# CyDAQ_schematic.net
KiCad netlist of a schematic drawn in EAGLE
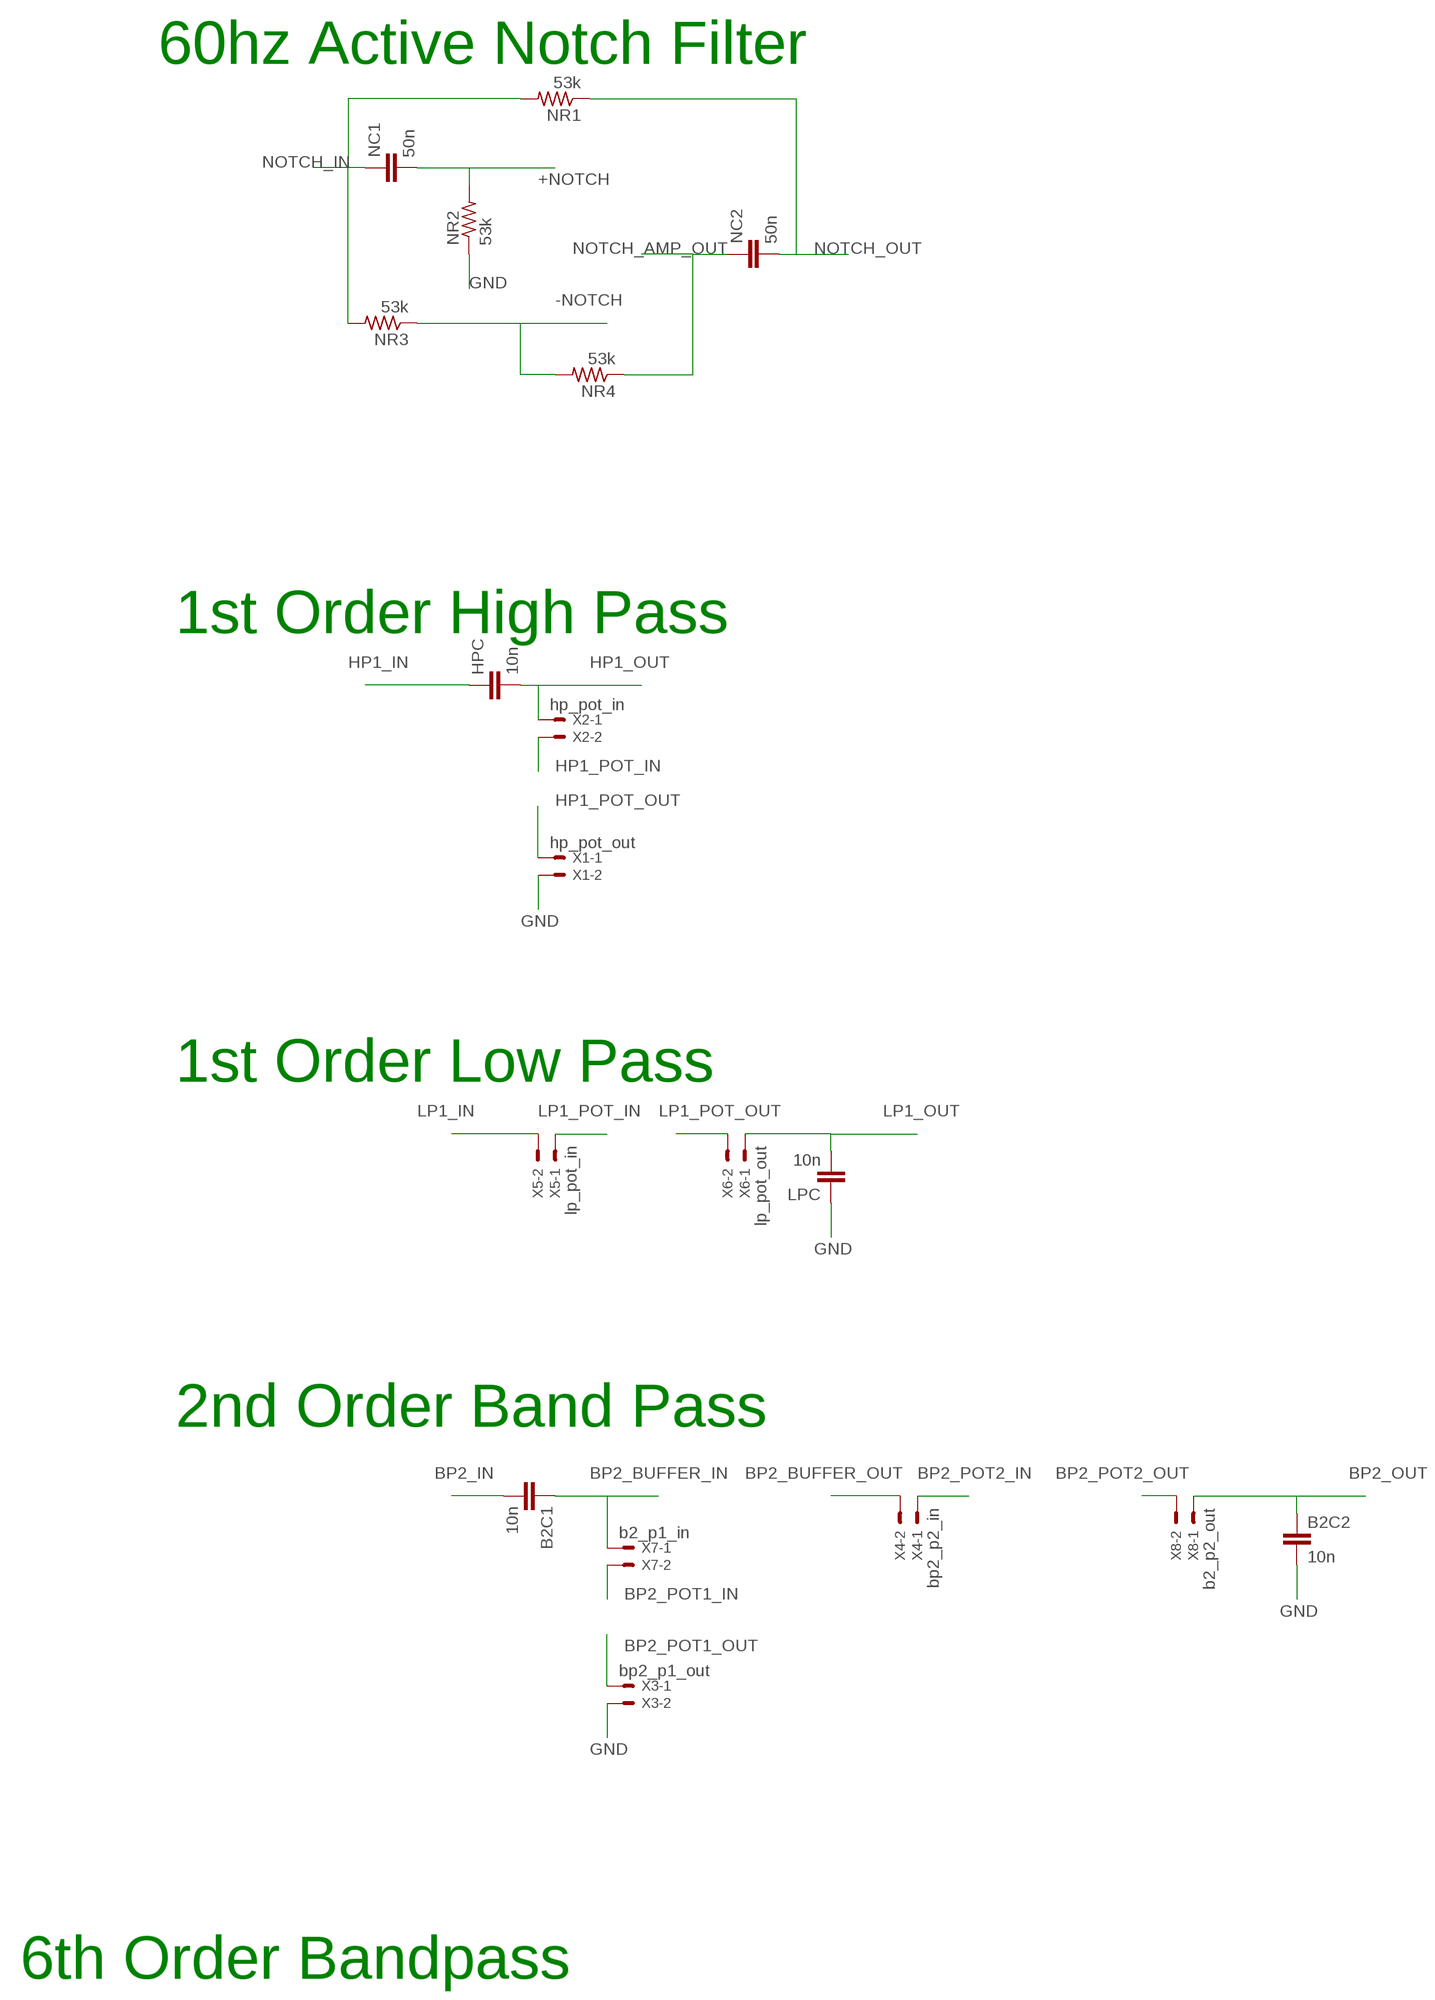
[diagram p0: schematic, sheet 1, part 1 of 3]
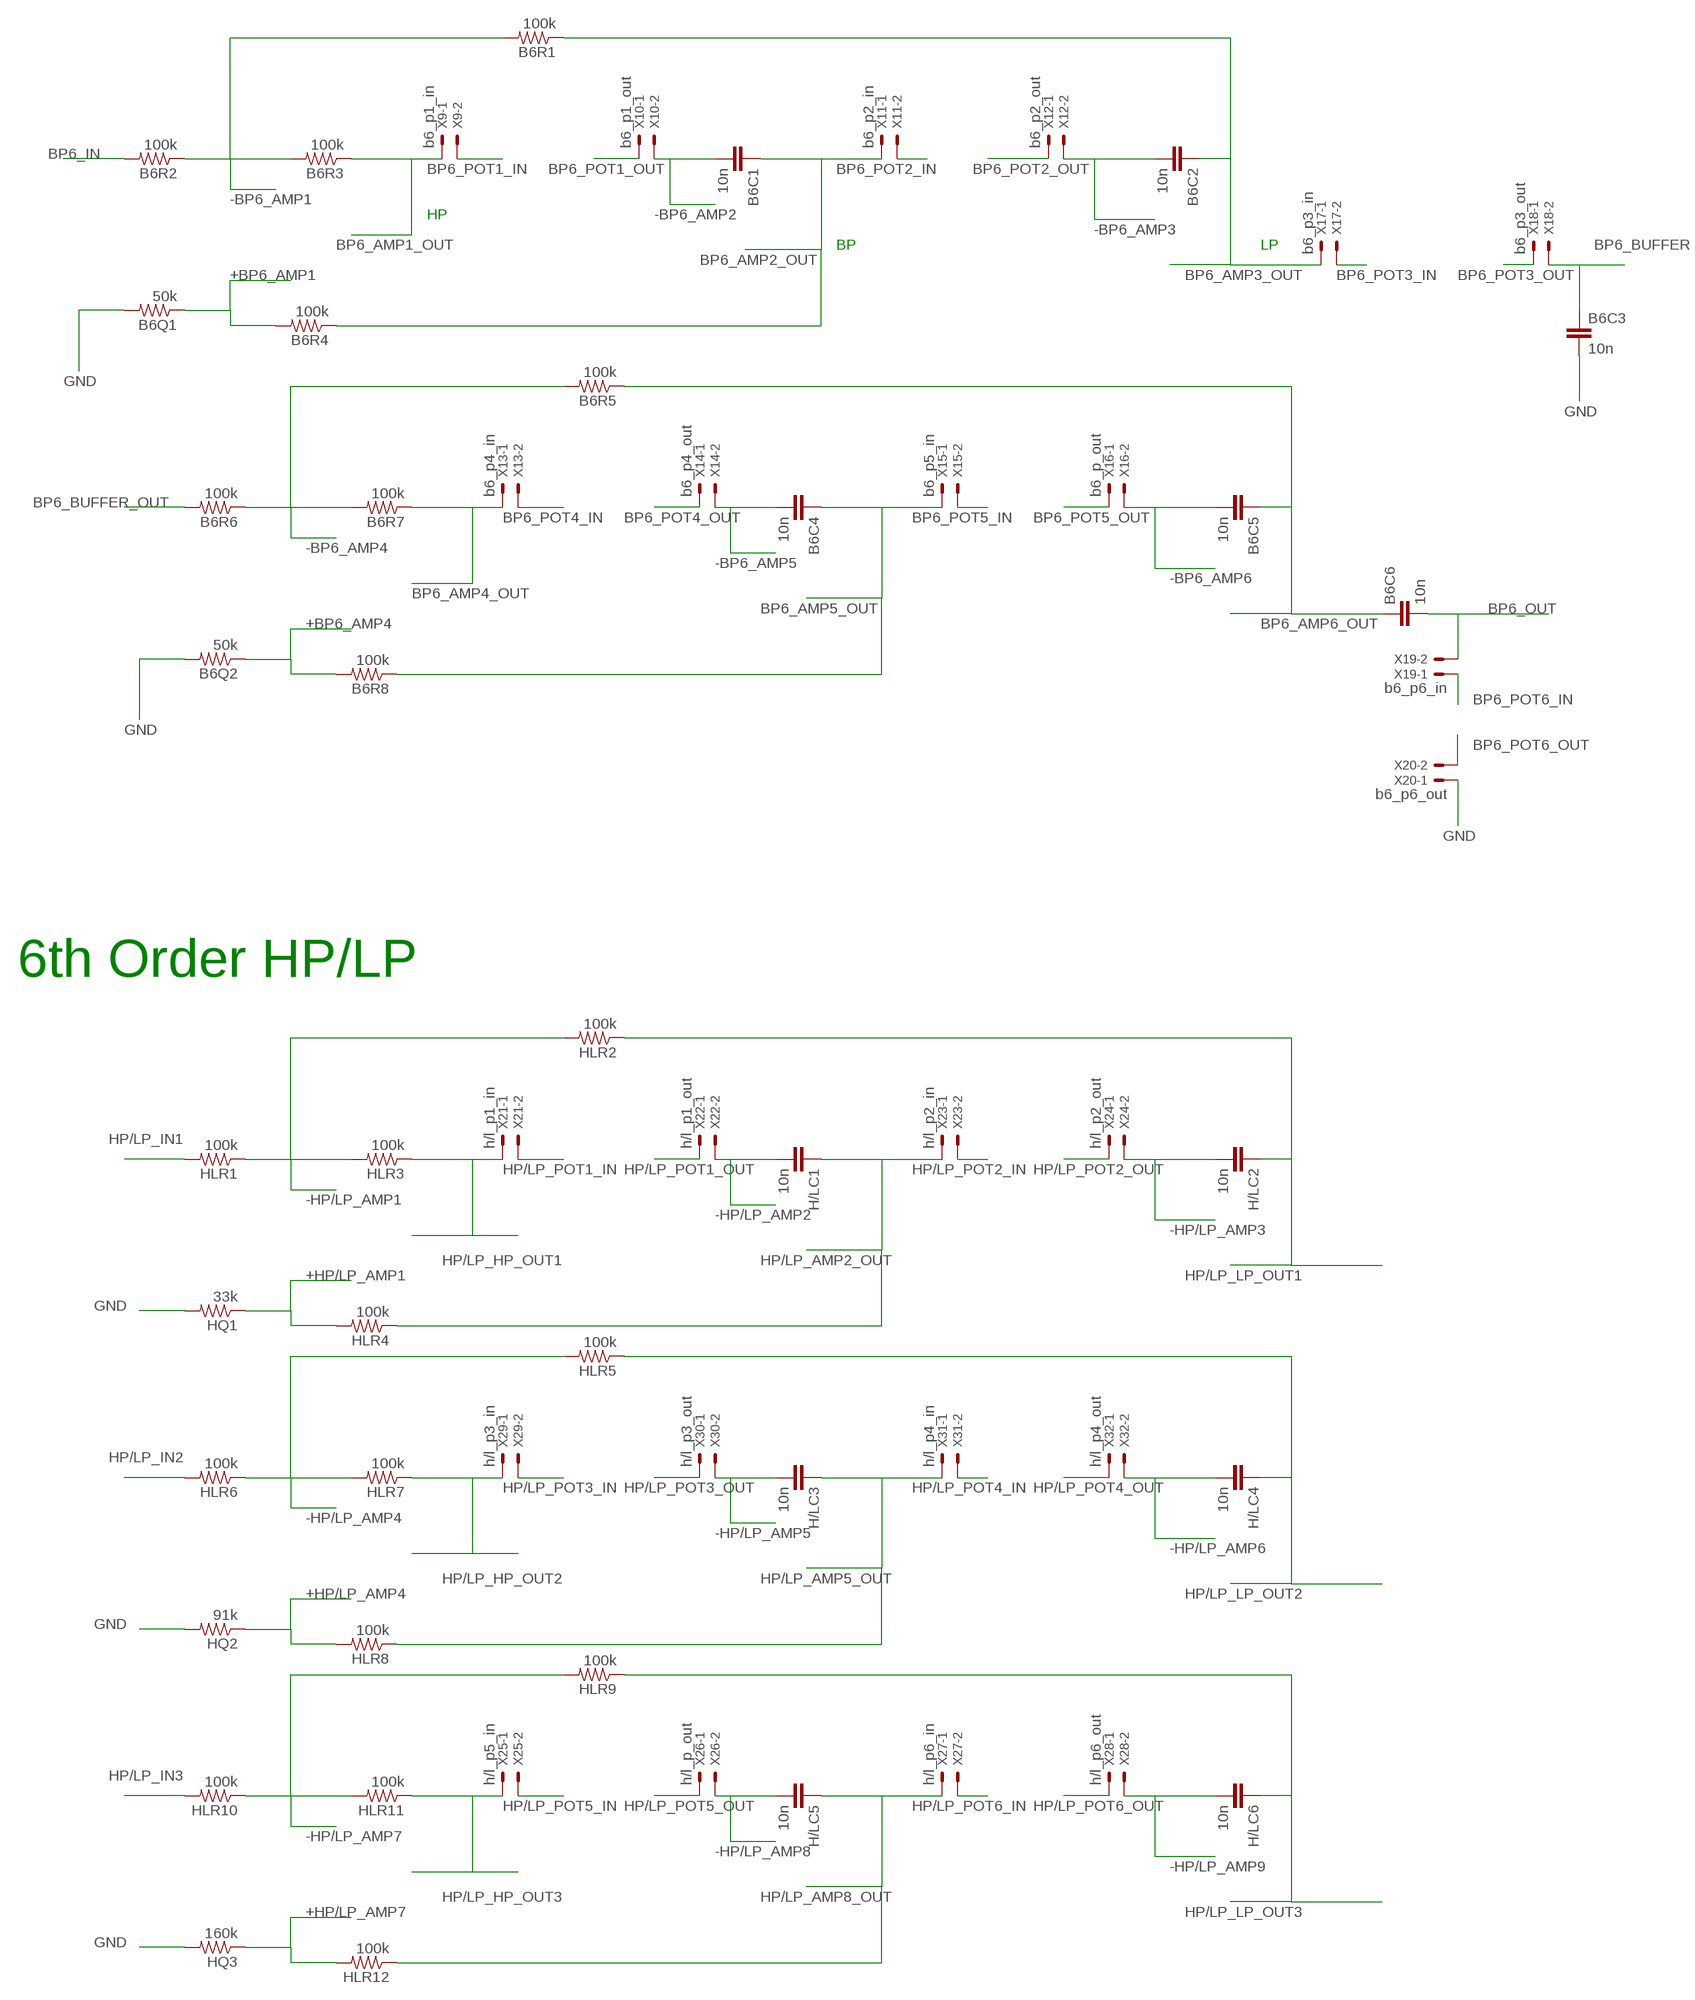
[diagram p1: schematic, sheet 1, part 2 of 3]
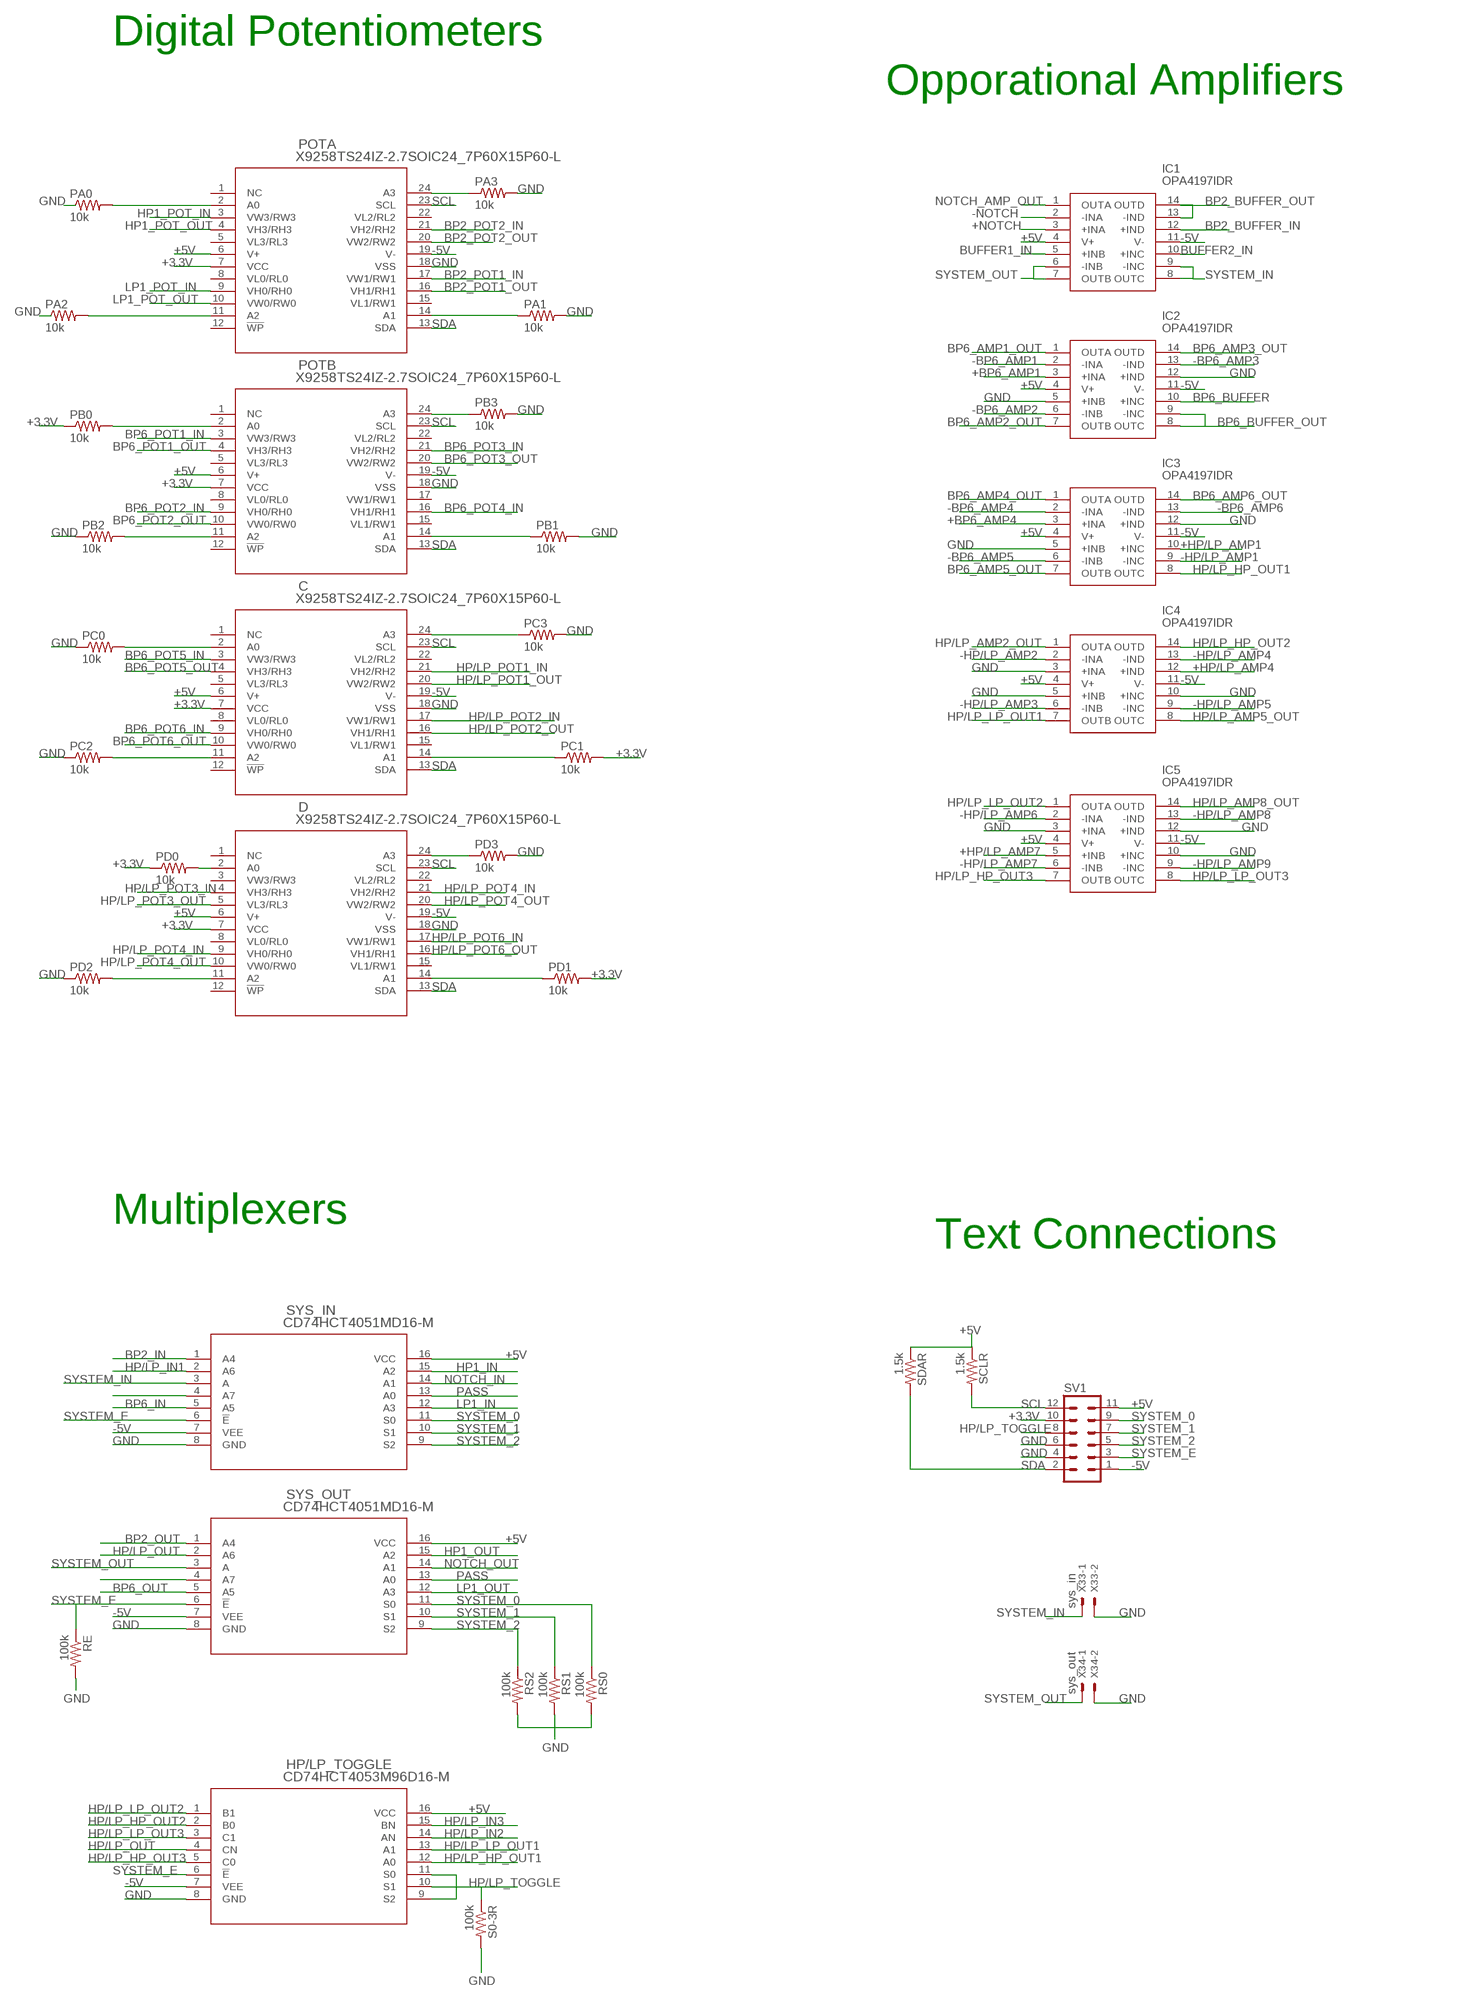
[diagram p2: schematic, sheet 1, part 3 of 3]

(export (version "E")
  (design (tool "Eeschema 10.0.6"))
  (components
    (comp (ref "B2C1")
      (value "10n")
      (footprint "eagle-import:C0805K")
      (libsource (lib "eagle-import") (part "C-EUC0805K"))
    )
    (comp (ref "B2C2")
      (value "10n")
      (footprint "eagle-import:C0805K")
      (libsource (lib "eagle-import") (part "C-EUC0805K"))
    )
    (comp (ref "B6C1")
      (value "10n")
      (footprint "eagle-import:C0805K")
      (libsource (lib "eagle-import") (part "C-EUC0805K"))
    )
    (comp (ref "B6C2")
      (value "10n")
      (footprint "eagle-import:C0805K")
      (libsource (lib "eagle-import") (part "C-EUC0805K"))
    )
    (comp (ref "B6C3")
      (value "10n")
      (footprint "eagle-import:C0805K")
      (libsource (lib "eagle-import") (part "C-EUC0805K"))
    )
    (comp (ref "B6C4")
      (value "10n")
      (footprint "eagle-import:C0805K")
      (libsource (lib "eagle-import") (part "C-EUC0805K"))
    )
    (comp (ref "B6C5")
      (value "10n")
      (footprint "eagle-import:C0805K")
      (libsource (lib "eagle-import") (part "C-EUC0805K"))
    )
    (comp (ref "B6C6")
      (value "10n")
      (footprint "eagle-import:C0805K")
      (libsource (lib "eagle-import") (part "C-EUC0805K"))
    )
    (comp (ref "B6Q1")
      (value "50k")
      (footprint "eagle-import:R0805W")
      (libsource (lib "eagle-import") (part "R-US_R0805W"))
    )
    (comp (ref "B6Q2")
      (value "50k")
      (footprint "eagle-import:R0805W")
      (libsource (lib "eagle-import") (part "R-US_R0805W"))
    )
    (comp (ref "B6R1")
      (value "100k")
      (footprint "eagle-import:R0805W")
      (libsource (lib "eagle-import") (part "R-US_R0805W"))
    )
    (comp (ref "B6R2")
      (value "100k")
      (footprint "eagle-import:R0805W")
      (libsource (lib "eagle-import") (part "R-US_R0805W"))
    )
    (comp (ref "B6R3")
      (value "100k")
      (footprint "eagle-import:R0805W")
      (libsource (lib "eagle-import") (part "R-US_R0805W"))
    )
    (comp (ref "B6R4")
      (value "100k")
      (footprint "eagle-import:R0805W")
      (libsource (lib "eagle-import") (part "R-US_R0805W"))
    )
    (comp (ref "B6R5")
      (value "100k")
      (footprint "eagle-import:R0805W")
      (libsource (lib "eagle-import") (part "R-US_R0805W"))
    )
    (comp (ref "B6R6")
      (value "100k")
      (footprint "eagle-import:R0805W")
      (libsource (lib "eagle-import") (part "R-US_R0805W"))
    )
    (comp (ref "B6R7")
      (value "100k")
      (footprint "eagle-import:R0805W")
      (libsource (lib "eagle-import") (part "R-US_R0805W"))
    )
    (comp (ref "B6R8")
      (value "100k")
      (footprint "eagle-import:R0805W")
      (libsource (lib "eagle-import") (part "R-US_R0805W"))
    )
    (comp (ref "C")
      (value "X9258TS24IZ-2.7SOIC24_7P60X15P60-L")
      (footprint "eagle-import:SOIC24_7P60X15P60-L")
      (fields (field (name "MANUFACTURER_PART_NUMBER") "X9258TS24IZ2.7"))
      (libsource (lib "eagle-import") (part "X9258TS24IZ-2.7SOIC24_7P60X15P60-L"))
    )
    (comp (ref "D")
      (value "X9258TS24IZ-2.7SOIC24_7P60X15P60-L")
      (footprint "eagle-import:SOIC24_7P60X15P60-L")
      (fields (field (name "MANUFACTURER_PART_NUMBER") "X9258TS24IZ2.7"))
      (libsource (lib "eagle-import") (part "X9258TS24IZ-2.7SOIC24_7P60X15P60-L"))
    )
    (comp (ref "H/LC1")
      (value "10n")
      (footprint "eagle-import:C0805K")
      (libsource (lib "eagle-import") (part "C-EUC0805K"))
    )
    (comp (ref "H/LC2")
      (value "10n")
      (footprint "eagle-import:C0805K")
      (libsource (lib "eagle-import") (part "C-EUC0805K"))
    )
    (comp (ref "H/LC3")
      (value "10n")
      (footprint "eagle-import:C0805K")
      (libsource (lib "eagle-import") (part "C-EUC0805K"))
    )
    (comp (ref "H/LC4")
      (value "10n")
      (footprint "eagle-import:C0805K")
      (libsource (lib "eagle-import") (part "C-EUC0805K"))
    )
    (comp (ref "H/LC5")
      (value "10n")
      (footprint "eagle-import:C0805K")
      (libsource (lib "eagle-import") (part "C-EUC0805K"))
    )
    (comp (ref "H/LC6")
      (value "10n")
      (footprint "eagle-import:C0805K")
      (libsource (lib "eagle-import") (part "C-EUC0805K"))
    )
    (comp (ref "HLR1")
      (value "100k")
      (footprint "eagle-import:R0805W")
      (libsource (lib "eagle-import") (part "R-US_R0805W"))
    )
    (comp (ref "HLR2")
      (value "100k")
      (footprint "eagle-import:R0805W")
      (libsource (lib "eagle-import") (part "R-US_R0805W"))
    )
    (comp (ref "HLR3")
      (value "100k")
      (footprint "eagle-import:R0805W")
      (libsource (lib "eagle-import") (part "R-US_R0805W"))
    )
    (comp (ref "HLR4")
      (value "100k")
      (footprint "eagle-import:R0805W")
      (libsource (lib "eagle-import") (part "R-US_R0805W"))
    )
    (comp (ref "HLR5")
      (value "100k")
      (footprint "eagle-import:R0805W")
      (libsource (lib "eagle-import") (part "R-US_R0805W"))
    )
    (comp (ref "HLR6")
      (value "100k")
      (footprint "eagle-import:R0805W")
      (libsource (lib "eagle-import") (part "R-US_R0805W"))
    )
    (comp (ref "HLR7")
      (value "100k")
      (footprint "eagle-import:R0805W")
      (libsource (lib "eagle-import") (part "R-US_R0805W"))
    )
    (comp (ref "HLR8")
      (value "100k")
      (footprint "eagle-import:R0805W")
      (libsource (lib "eagle-import") (part "R-US_R0805W"))
    )
    (comp (ref "HLR9")
      (value "100k")
      (footprint "eagle-import:R0805W")
      (libsource (lib "eagle-import") (part "R-US_R0805W"))
    )
    (comp (ref "HLR10")
      (value "100k")
      (footprint "eagle-import:R0805W")
      (libsource (lib "eagle-import") (part "R-US_R0805W"))
    )
    (comp (ref "HLR11")
      (value "100k")
      (footprint "eagle-import:R0805W")
      (libsource (lib "eagle-import") (part "R-US_R0805W"))
    )
    (comp (ref "HLR12")
      (value "100k")
      (footprint "eagle-import:R0805W")
      (libsource (lib "eagle-import") (part "R-US_R0805W"))
    )
    (comp (ref "HP/LP_TOGGLE")
      (value "CD74HCT4053M96D16-M")
      (footprint "eagle-import:D16-M")
      (fields (field (name "MANUFACTURER_PART_NUMBER") "CD74HCT4053M96"))
      (libsource (lib "eagle-import") (part "CD74HCT4053M96D16-M"))
    )
    (comp (ref "HPC")
      (value "10n")
      (footprint "eagle-import:C0805K")
      (libsource (lib "eagle-import") (part "C-EUC0805K"))
    )
    (comp (ref "HQ1")
      (value "33k")
      (footprint "eagle-import:R0805W")
      (libsource (lib "eagle-import") (part "R-US_R0805W"))
    )
    (comp (ref "HQ2")
      (value "91k")
      (footprint "eagle-import:R0805W")
      (libsource (lib "eagle-import") (part "R-US_R0805W"))
    )
    (comp (ref "HQ3")
      (value "160k")
      (footprint "eagle-import:R0805W")
      (libsource (lib "eagle-import") (part "R-US_R0805W"))
    )
    (comp (ref "IC1")
      (value "OPA4197IDR")
      (footprint "eagle-import:SOIC127P600X175-14N")
      (fields (field (name "MOUSER_PART_NUMBER") "595-OPA4197IDR"))
      (libsource (lib "eagle-import") (part "OPA4197IDR"))
    )
    (comp (ref "IC2")
      (value "OPA4197IDR")
      (footprint "eagle-import:SOIC127P600X175-14N")
      (fields (field (name "MOUSER_PART_NUMBER") "595-OPA4197IDR"))
      (libsource (lib "eagle-import") (part "OPA4197IDR"))
    )
    (comp (ref "IC3")
      (value "OPA4197IDR")
      (footprint "eagle-import:SOIC127P600X175-14N")
      (fields (field (name "MOUSER_PART_NUMBER") "595-OPA4197IDR"))
      (libsource (lib "eagle-import") (part "OPA4197IDR"))
    )
    (comp (ref "IC4")
      (value "OPA4197IDR")
      (footprint "eagle-import:SOIC127P600X175-14N")
      (fields (field (name "MOUSER_PART_NUMBER") "595-OPA4197IDR"))
      (libsource (lib "eagle-import") (part "OPA4197IDR"))
    )
    (comp (ref "IC5")
      (value "OPA4197IDR")
      (footprint "eagle-import:SOIC127P600X175-14N")
      (fields (field (name "MOUSER_PART_NUMBER") "595-OPA4197IDR"))
      (libsource (lib "eagle-import") (part "OPA4197IDR"))
    )
    (comp (ref "LPC")
      (value "10n")
      (footprint "eagle-import:C0805K")
      (libsource (lib "eagle-import") (part "C-EUC0805K"))
    )
    (comp (ref "NC1")
      (value "50n")
      (footprint "eagle-import:C0805K")
      (libsource (lib "eagle-import") (part "C-EUC0805K"))
    )
    (comp (ref "NC2")
      (value "50n")
      (footprint "eagle-import:C0805K")
      (libsource (lib "eagle-import") (part "C-EUC0805K"))
    )
    (comp (ref "NR1")
      (value "53k")
      (footprint "eagle-import:R0805W")
      (libsource (lib "eagle-import") (part "R-US_R0805W"))
    )
    (comp (ref "NR2")
      (value "53k")
      (footprint "eagle-import:R0805W")
      (libsource (lib "eagle-import") (part "R-US_R0805W"))
    )
    (comp (ref "NR3")
      (value "53k")
      (footprint "eagle-import:R0805W")
      (libsource (lib "eagle-import") (part "R-US_R0805W"))
    )
    (comp (ref "NR4")
      (value "53k")
      (footprint "eagle-import:R0805W")
      (libsource (lib "eagle-import") (part "R-US_R0805W"))
    )
    (comp (ref "PA0")
      (value "10k")
      (footprint "eagle-import:R0805W")
      (libsource (lib "eagle-import") (part "R-US_R0805W"))
    )
    (comp (ref "PA1")
      (value "10k")
      (footprint "eagle-import:R0805W")
      (libsource (lib "eagle-import") (part "R-US_R0805W"))
    )
    (comp (ref "PA2")
      (value "10k")
      (footprint "eagle-import:R0805W")
      (libsource (lib "eagle-import") (part "R-US_R0805W"))
    )
    (comp (ref "PA3")
      (value "10k")
      (footprint "eagle-import:R0805W")
      (libsource (lib "eagle-import") (part "R-US_R0805W"))
    )
    (comp (ref "PB0")
      (value "10k")
      (footprint "eagle-import:R0805W")
      (libsource (lib "eagle-import") (part "R-US_R0805W"))
    )
    (comp (ref "PB1")
      (value "10k")
      (footprint "eagle-import:R0805W")
      (libsource (lib "eagle-import") (part "R-US_R0805W"))
    )
    (comp (ref "PB2")
      (value "10k")
      (footprint "eagle-import:R0805W")
      (libsource (lib "eagle-import") (part "R-US_R0805W"))
    )
    (comp (ref "PB3")
      (value "10k")
      (footprint "eagle-import:R0805W")
      (libsource (lib "eagle-import") (part "R-US_R0805W"))
    )
    (comp (ref "PC0")
      (value "10k")
      (footprint "eagle-import:R0805W")
      (libsource (lib "eagle-import") (part "R-US_R0805W"))
    )
    (comp (ref "PC1")
      (value "10k")
      (footprint "eagle-import:R0805W")
      (libsource (lib "eagle-import") (part "R-US_R0805W"))
    )
    (comp (ref "PC2")
      (value "10k")
      (footprint "eagle-import:R0805W")
      (libsource (lib "eagle-import") (part "R-US_R0805W"))
    )
    (comp (ref "PC3")
      (value "10k")
      (footprint "eagle-import:R0805W")
      (libsource (lib "eagle-import") (part "R-US_R0805W"))
    )
    (comp (ref "PD0")
      (value "10k")
      (footprint "eagle-import:R0805W")
      (libsource (lib "eagle-import") (part "R-US_R0805W"))
    )
    (comp (ref "PD1")
      (value "10k")
      (footprint "eagle-import:R0805W")
      (libsource (lib "eagle-import") (part "R-US_R0805W"))
    )
    (comp (ref "PD2")
      (value "10k")
      (footprint "eagle-import:R0805W")
      (libsource (lib "eagle-import") (part "R-US_R0805W"))
    )
    (comp (ref "PD3")
      (value "10k")
      (footprint "eagle-import:R0805W")
      (libsource (lib "eagle-import") (part "R-US_R0805W"))
    )
    (comp (ref "POTA")
      (value "X9258TS24IZ-2.7SOIC24_7P60X15P60-L")
      (footprint "eagle-import:SOIC24_7P60X15P60-L")
      (fields (field (name "MANUFACTURER_PART_NUMBER") "X9258TS24IZ2.7"))
      (libsource (lib "eagle-import") (part "X9258TS24IZ-2.7SOIC24_7P60X15P60-L"))
    )
    (comp (ref "POTB")
      (value "X9258TS24IZ-2.7SOIC24_7P60X15P60-L")
      (footprint "eagle-import:SOIC24_7P60X15P60-L")
      (fields (field (name "MANUFACTURER_PART_NUMBER") "X9258TS24IZ2.7"))
      (libsource (lib "eagle-import") (part "X9258TS24IZ-2.7SOIC24_7P60X15P60-L"))
    )
    (comp (ref "RE")
      (value "100k")
      (footprint "eagle-import:R0805W")
      (libsource (lib "eagle-import") (part "R-US_R0805W"))
    )
    (comp (ref "RS0")
      (value "100k")
      (footprint "eagle-import:R0805W")
      (libsource (lib "eagle-import") (part "R-US_R0805W"))
    )
    (comp (ref "RS1")
      (value "100k")
      (footprint "eagle-import:R0805W")
      (libsource (lib "eagle-import") (part "R-US_R0805W"))
    )
    (comp (ref "RS2")
      (value "100k")
      (footprint "eagle-import:R0805W")
      (libsource (lib "eagle-import") (part "R-US_R0805W"))
    )
    (comp (ref "S0-3R")
      (value "100k")
      (footprint "eagle-import:R0805W")
      (libsource (lib "eagle-import") (part "R-US_R0805W"))
    )
    (comp (ref "SCLR")
      (value "1.5k")
      (footprint "eagle-import:R0805W")
      (libsource (lib "eagle-import") (part "R-US_R0805W"))
    )
    (comp (ref "SDAR")
      (value "1.5k")
      (footprint "eagle-import:R0805W")
      (libsource (lib "eagle-import") (part "R-US_R0805W"))
    )
    (comp (ref "SV1")
      (value "MA06-2")
      (footprint "eagle-import:MA06-2")
      (libsource (lib "eagle-import") (part "MA06-2"))
    )
    (comp (ref "SYS_IN")
      (value "CD74HCT4051MD16-M")
      (footprint "eagle-import:D16-M")
      (fields (field (name "MANUFACTURER_PART_NUMBER") "CD74HCT4051M"))
      (libsource (lib "eagle-import") (part "CD74HCT4051MD16-M"))
    )
    (comp (ref "SYS_OUT")
      (value "CD74HCT4051MD16-M")
      (footprint "eagle-import:D16-M")
      (fields (field (name "MANUFACTURER_PART_NUMBER") "CD74HCT4051M"))
      (libsource (lib "eagle-import") (part "CD74HCT4051MD16-M"))
    )
    (comp (ref "X1")
      (value "hp_pot_out")
      (footprint "eagle-import:22-23-2021")
      (fields (field (name "MF") "MOLEX") (field (name "MPN") "22-23-2021"))
      (libsource (lib "eagle-import") (part "22-23-2021"))
    )
    (comp (ref "X2")
      (value "hp_pot_in")
      (footprint "eagle-import:22-23-2021")
      (fields (field (name "MF") "MOLEX") (field (name "MPN") "22-23-2021"))
      (libsource (lib "eagle-import") (part "22-23-2021"))
    )
    (comp (ref "X3")
      (value "bp2_p1_out")
      (footprint "eagle-import:22-23-2021")
      (fields (field (name "MF") "MOLEX") (field (name "MPN") "22-23-2021"))
      (libsource (lib "eagle-import") (part "22-23-2021"))
    )
    (comp (ref "X4")
      (value "bp2_p2_in")
      (footprint "eagle-import:22-23-2021")
      (fields (field (name "MF") "MOLEX") (field (name "MPN") "22-23-2021"))
      (libsource (lib "eagle-import") (part "22-23-2021"))
    )
    (comp (ref "X5")
      (value "lp_pot_in")
      (footprint "eagle-import:22-23-2021")
      (fields (field (name "MF") "MOLEX") (field (name "MPN") "22-23-2021"))
      (libsource (lib "eagle-import") (part "22-23-2021"))
    )
    (comp (ref "X6")
      (value "lp_pot_out")
      (footprint "eagle-import:22-23-2021")
      (fields (field (name "MF") "MOLEX") (field (name "MPN") "22-23-2021"))
      (libsource (lib "eagle-import") (part "22-23-2021"))
    )
    (comp (ref "X7")
      (value "b2_p1_in")
      (footprint "eagle-import:22-23-2021")
      (fields (field (name "MF") "MOLEX") (field (name "MPN") "22-23-2021"))
      (libsource (lib "eagle-import") (part "22-23-2021"))
    )
    (comp (ref "X8")
      (value "b2_p2_out")
      (footprint "eagle-import:22-23-2021")
      (fields (field (name "MF") "MOLEX") (field (name "MPN") "22-23-2021"))
      (libsource (lib "eagle-import") (part "22-23-2021"))
    )
    (comp (ref "X9")
      (value "b6_p1_in")
      (footprint "eagle-import:22-23-2021")
      (fields (field (name "MF") "MOLEX") (field (name "MPN") "22-23-2021"))
      (libsource (lib "eagle-import") (part "22-23-2021"))
    )
    (comp (ref "X10")
      (value "b6_p1_out")
      (footprint "eagle-import:22-23-2021")
      (fields (field (name "MF") "MOLEX") (field (name "MPN") "22-23-2021"))
      (libsource (lib "eagle-import") (part "22-23-2021"))
    )
    (comp (ref "X11")
      (value "b6_p2_in")
      (footprint "eagle-import:22-23-2021")
      (fields (field (name "MF") "MOLEX") (field (name "MPN") "22-23-2021"))
      (libsource (lib "eagle-import") (part "22-23-2021"))
    )
    (comp (ref "X12")
      (value "b6_p2_out")
      (footprint "eagle-import:22-23-2021")
      (fields (field (name "MF") "MOLEX") (field (name "MPN") "22-23-2021"))
      (libsource (lib "eagle-import") (part "22-23-2021"))
    )
    (comp (ref "X13")
      (value "b6_p4_in")
      (footprint "eagle-import:22-23-2021")
      (fields (field (name "MF") "MOLEX") (field (name "MPN") "22-23-2021"))
      (libsource (lib "eagle-import") (part "22-23-2021"))
    )
    (comp (ref "X14")
      (value "b6_p4_out")
      (footprint "eagle-import:22-23-2021")
      (fields (field (name "MF") "MOLEX") (field (name "MPN") "22-23-2021"))
      (libsource (lib "eagle-import") (part "22-23-2021"))
    )
    (comp (ref "X15")
      (value "b6_p5_in")
      (footprint "eagle-import:22-23-2021")
      (fields (field (name "MF") "MOLEX") (field (name "MPN") "22-23-2021"))
      (libsource (lib "eagle-import") (part "22-23-2021"))
    )
    (comp (ref "X16")
      (value "b6_p_out")
      (footprint "eagle-import:22-23-2021")
      (fields (field (name "MF") "MOLEX") (field (name "MPN") "22-23-2021"))
      (libsource (lib "eagle-import") (part "22-23-2021"))
    )
    (comp (ref "X17")
      (value "b6_p3_in")
      (footprint "eagle-import:22-23-2021")
      (fields (field (name "MF") "MOLEX") (field (name "MPN") "22-23-2021"))
      (libsource (lib "eagle-import") (part "22-23-2021"))
    )
    (comp (ref "X18")
      (value "b6_p3_out")
      (footprint "eagle-import:22-23-2021")
      (fields (field (name "MF") "MOLEX") (field (name "MPN") "22-23-2021"))
      (libsource (lib "eagle-import") (part "22-23-2021"))
    )
    (comp (ref "X19")
      (value "b6_p6_in")
      (footprint "eagle-import:22-23-2021")
      (fields (field (name "MF") "MOLEX") (field (name "MPN") "22-23-2021"))
      (libsource (lib "eagle-import") (part "22-23-2021"))
    )
    (comp (ref "X20")
      (value "b6_p6_out")
      (footprint "eagle-import:22-23-2021")
      (fields (field (name "MF") "MOLEX") (field (name "MPN") "22-23-2021"))
      (libsource (lib "eagle-import") (part "22-23-2021"))
    )
    (comp (ref "X21")
      (value "h/l_p1_in")
      (footprint "eagle-import:22-23-2021")
      (fields (field (name "MF") "MOLEX") (field (name "MPN") "22-23-2021"))
      (libsource (lib "eagle-import") (part "22-23-2021"))
    )
    (comp (ref "X22")
      (value "h/l_p1_out")
      (footprint "eagle-import:22-23-2021")
      (fields (field (name "MF") "MOLEX") (field (name "MPN") "22-23-2021"))
      (libsource (lib "eagle-import") (part "22-23-2021"))
    )
    (comp (ref "X23")
      (value "h/l_p2_in")
      (footprint "eagle-import:22-23-2021")
      (fields (field (name "MF") "MOLEX") (field (name "MPN") "22-23-2021"))
      (libsource (lib "eagle-import") (part "22-23-2021"))
    )
    (comp (ref "X24")
      (value "h/l_p2_out")
      (footprint "eagle-import:22-23-2021")
      (fields (field (name "MF") "MOLEX") (field (name "MPN") "22-23-2021"))
      (libsource (lib "eagle-import") (part "22-23-2021"))
    )
    (comp (ref "X25")
      (value "h/l_p5_in")
      (footprint "eagle-import:22-23-2021")
      (fields (field (name "MF") "MOLEX") (field (name "MPN") "22-23-2021"))
      (libsource (lib "eagle-import") (part "22-23-2021"))
    )
    (comp (ref "X26")
      (value "h/l_p_out")
      (footprint "eagle-import:22-23-2021")
      (fields (field (name "MF") "MOLEX") (field (name "MPN") "22-23-2021"))
      (libsource (lib "eagle-import") (part "22-23-2021"))
    )
    (comp (ref "X27")
      (value "h/l_p6_in")
      (footprint "eagle-import:22-23-2021")
      (fields (field (name "MF") "MOLEX") (field (name "MPN") "22-23-2021"))
      (libsource (lib "eagle-import") (part "22-23-2021"))
    )
    (comp (ref "X28")
      (value "h/l_p6_out")
      (footprint "eagle-import:22-23-2021")
      (fields (field (name "MF") "MOLEX") (field (name "MPN") "22-23-2021"))
      (libsource (lib "eagle-import") (part "22-23-2021"))
    )
    (comp (ref "X29")
      (value "h/l_p3_in")
      (footprint "eagle-import:22-23-2021")
      (fields (field (name "MF") "MOLEX") (field (name "MPN") "22-23-2021"))
      (libsource (lib "eagle-import") (part "22-23-2021"))
    )
    (comp (ref "X30")
      (value "h/l_p3_out")
      (footprint "eagle-import:22-23-2021")
      (fields (field (name "MF") "MOLEX") (field (name "MPN") "22-23-2021"))
      (libsource (lib "eagle-import") (part "22-23-2021"))
    )
    (comp (ref "X31")
      (value "h/l_p4_in")
      (footprint "eagle-import:22-23-2021")
      (fields (field (name "MF") "MOLEX") (field (name "MPN") "22-23-2021"))
      (libsource (lib "eagle-import") (part "22-23-2021"))
    )
    (comp (ref "X32")
      (value "h/l_p4_out")
      (footprint "eagle-import:22-23-2021")
      (fields (field (name "MF") "MOLEX") (field (name "MPN") "22-23-2021"))
      (libsource (lib "eagle-import") (part "22-23-2021"))
    )
    (comp (ref "X33")
      (value "sys_in")
      (footprint "eagle-import:22-23-2021")
      (fields (field (name "MF") "MOLEX") (field (name "MPN") "22-23-2021"))
      (libsource (lib "eagle-import") (part "22-23-2021"))
    )
    (comp (ref "X34")
      (value "sys_out")
      (footprint "eagle-import:22-23-2021")
      (fields (field (name "MF") "MOLEX") (field (name "MPN") "22-23-2021"))
      (libsource (lib "eagle-import") (part "22-23-2021"))
    )
  )
  (nets
    (net (code "1") (name "/+3.3V") (class "Default")
      (node (ref "C") (pin "7") (pinfunction "VCC_7") (pintype "power_in"))
      (node (ref "D") (pin "7") (pinfunction "VCC_7") (pintype "power_in"))
      (node (ref "PB0") (pin "1") (pinfunction "1_1") (pintype "passive"))
      (node (ref "PC1") (pin "2") (pinfunction "2_2") (pintype "passive"))
      (node (ref "PD0") (pin "1") (pinfunction "1_1") (pintype "passive"))
      (node (ref "PD1") (pin "2") (pinfunction "2_2") (pintype "passive"))
      (node (ref "POTA") (pin "7") (pinfunction "VCC_7") (pintype "power_in"))
      (node (ref "POTB") (pin "7") (pinfunction "VCC_7") (pintype "power_in"))
      (node (ref "SV1") (pin "10") (pinfunction "10_10") (pintype "passive"))
    )
    (net (code "2") (name "/+5V") (class "Default")
      (node (ref "C") (pin "6") (pinfunction "V+_6") (pintype "power_in"))
      (node (ref "D") (pin "6") (pinfunction "V+_6") (pintype "power_in"))
      (node (ref "HP/LP_TOGGLE") (pin "16") (pinfunction "VCC_16") (pintype "power_in"))
      (node (ref "IC1") (pin "4") (pinfunction "V+_4") (pintype "power_in"))
      (node (ref "IC2") (pin "4") (pinfunction "V+_4") (pintype "power_in"))
      (node (ref "IC3") (pin "4") (pinfunction "V+_4") (pintype "power_in"))
      (node (ref "IC4") (pin "4") (pinfunction "V+_4") (pintype "power_in"))
      (node (ref "IC5") (pin "4") (pinfunction "V+_4") (pintype "power_in"))
      (node (ref "POTA") (pin "6") (pinfunction "V+_6") (pintype "power_in"))
      (node (ref "POTB") (pin "6") (pinfunction "V+_6") (pintype "power_in"))
      (node (ref "SCLR") (pin "1") (pinfunction "1_1") (pintype "passive"))
      (node (ref "SDAR") (pin "1") (pinfunction "1_1") (pintype "passive"))
      (node (ref "SV1") (pin "11") (pinfunction "11_11") (pintype "passive"))
      (node (ref "SYS_IN") (pin "16") (pinfunction "VCC_16") (pintype "power_in"))
      (node (ref "SYS_OUT") (pin "16") (pinfunction "VCC_16") (pintype "power_in"))
    )
    (net (code "3") (name "/+BP6_AMP1") (class "Default")
      (node (ref "B6Q1") (pin "1") (pinfunction "1_1") (pintype "passive"))
      (node (ref "B6R4") (pin "2") (pinfunction "2_2") (pintype "passive"))
      (node (ref "IC2") (pin "3") (pinfunction "+INA_3") (pintype "input"))
    )
    (net (code "4") (name "/+BP6_AMP4") (class "Default")
      (node (ref "B6Q2") (pin "1") (pinfunction "1_1") (pintype "passive"))
      (node (ref "B6R8") (pin "2") (pinfunction "2_2") (pintype "passive"))
      (node (ref "IC3") (pin "3") (pinfunction "+INA_3") (pintype "input"))
    )
    (net (code "5") (name "/+HP{slash}LP_AMP1") (class "Default")
      (node (ref "HLR4") (pin "2") (pinfunction "2_2") (pintype "passive"))
      (node (ref "HQ1") (pin "1") (pinfunction "1_1") (pintype "passive"))
      (node (ref "IC3") (pin "10") (pinfunction "+INC_10") (pintype "input"))
    )
    (net (code "6") (name "/+HP{slash}LP_AMP4") (class "Default")
      (node (ref "HLR8") (pin "2") (pinfunction "2_2") (pintype "passive"))
      (node (ref "HQ2") (pin "1") (pinfunction "1_1") (pintype "passive"))
      (node (ref "IC4") (pin "12") (pinfunction "+IND_12") (pintype "input"))
    )
    (net (code "7") (name "/+HP{slash}LP_AMP7") (class "Default")
      (node (ref "HLR12") (pin "2") (pinfunction "2_2") (pintype "passive"))
      (node (ref "HQ3") (pin "1") (pinfunction "1_1") (pintype "passive"))
      (node (ref "IC5") (pin "5") (pinfunction "+INB_5") (pintype "input"))
    )
    (net (code "8") (name "/+NOTCH") (class "Default")
      (node (ref "IC1") (pin "3") (pinfunction "+INA_3") (pintype "input"))
      (node (ref "NC1") (pin "2") (pinfunction "2_2") (pintype "passive"))
      (node (ref "NR2") (pin "2") (pinfunction "2_2") (pintype "passive"))
    )
    (net (code "9") (name "/-5V") (class "Default")
      (node (ref "C") (pin "19") (pinfunction "V-_19") (pintype "power_in"))
      (node (ref "D") (pin "19") (pinfunction "V-_19") (pintype "power_in"))
      (node (ref "HP/LP_TOGGLE") (pin "7") (pinfunction "VEE_7") (pintype "power_in"))
      (node (ref "IC1") (pin "11") (pinfunction "V-_11") (pintype "power_in"))
      (node (ref "IC2") (pin "11") (pinfunction "V-_11") (pintype "power_in"))
      (node (ref "IC3") (pin "11") (pinfunction "V-_11") (pintype "power_in"))
      (node (ref "IC4") (pin "11") (pinfunction "V-_11") (pintype "power_in"))
      (node (ref "IC5") (pin "11") (pinfunction "V-_11") (pintype "power_in"))
      (node (ref "POTA") (pin "19") (pinfunction "V-_19") (pintype "power_in"))
      (node (ref "POTB") (pin "19") (pinfunction "V-_19") (pintype "power_in"))
      (node (ref "SV1") (pin "1") (pinfunction "1_1") (pintype "passive"))
      (node (ref "SYS_IN") (pin "7") (pinfunction "VEE_7") (pintype "power_in"))
      (node (ref "SYS_OUT") (pin "7") (pinfunction "VEE_7") (pintype "power_in"))
    )
    (net (code "10") (name "/-BP6_AMP1") (class "Default")
      (node (ref "B6R1") (pin "2") (pinfunction "2_2") (pintype "passive"))
      (node (ref "B6R2") (pin "1") (pinfunction "1_1") (pintype "passive"))
      (node (ref "B6R3") (pin "2") (pinfunction "2_2") (pintype "passive"))
      (node (ref "IC2") (pin "2") (pinfunction "-INA_2") (pintype "input"))
    )
    (net (code "11") (name "/-BP6_AMP2") (class "Default")
      (node (ref "B6C1") (pin "2") (pinfunction "2_2") (pintype "passive"))
      (node (ref "IC2") (pin "6") (pinfunction "-INB_6") (pintype "input"))
      (node (ref "X10") (pin "2") (pinfunction "S_2") (pintype "passive"))
    )
    (net (code "12") (name "/-BP6_AMP3") (class "Default")
      (node (ref "B6C2") (pin "2") (pinfunction "2_2") (pintype "passive"))
      (node (ref "IC2") (pin "13") (pinfunction "-IND_13") (pintype "input"))
      (node (ref "X12") (pin "2") (pinfunction "S_2") (pintype "passive"))
    )
    (net (code "13") (name "/-BP6_AMP4") (class "Default")
      (node (ref "B6R5") (pin "2") (pinfunction "2_2") (pintype "passive"))
      (node (ref "B6R6") (pin "1") (pinfunction "1_1") (pintype "passive"))
      (node (ref "B6R7") (pin "2") (pinfunction "2_2") (pintype "passive"))
      (node (ref "IC3") (pin "2") (pinfunction "-INA_2") (pintype "input"))
    )
    (net (code "14") (name "/-BP6_AMP5") (class "Default")
      (node (ref "B6C4") (pin "2") (pinfunction "2_2") (pintype "passive"))
      (node (ref "IC3") (pin "6") (pinfunction "-INB_6") (pintype "input"))
      (node (ref "X14") (pin "2") (pinfunction "S_2") (pintype "passive"))
    )
    (net (code "15") (name "/-BP6_AMP6") (class "Default")
      (node (ref "B6C5") (pin "2") (pinfunction "2_2") (pintype "passive"))
      (node (ref "IC3") (pin "13") (pinfunction "-IND_13") (pintype "input"))
      (node (ref "X16") (pin "2") (pinfunction "S_2") (pintype "passive"))
    )
    (net (code "16") (name "/-HP{slash}LP_AMP1") (class "Default")
      (node (ref "HLR1") (pin "1") (pinfunction "1_1") (pintype "passive"))
      (node (ref "HLR2") (pin "2") (pinfunction "2_2") (pintype "passive"))
      (node (ref "HLR3") (pin "2") (pinfunction "2_2") (pintype "passive"))
      (node (ref "IC3") (pin "9") (pinfunction "-INC_9") (pintype "input"))
    )
    (net (code "17") (name "/-HP{slash}LP_AMP2") (class "Default")
      (node (ref "H/LC1") (pin "2") (pinfunction "2_2") (pintype "passive"))
      (node (ref "IC4") (pin "2") (pinfunction "-INA_2") (pintype "input"))
      (node (ref "X22") (pin "2") (pinfunction "S_2") (pintype "passive"))
    )
    (net (code "18") (name "/-HP{slash}LP_AMP3") (class "Default")
      (node (ref "H/LC2") (pin "2") (pinfunction "2_2") (pintype "passive"))
      (node (ref "IC4") (pin "6") (pinfunction "-INB_6") (pintype "input"))
      (node (ref "X24") (pin "2") (pinfunction "S_2") (pintype "passive"))
    )
    (net (code "19") (name "/-HP{slash}LP_AMP4") (class "Default")
      (node (ref "HLR5") (pin "2") (pinfunction "2_2") (pintype "passive"))
      (node (ref "HLR6") (pin "1") (pinfunction "1_1") (pintype "passive"))
      (node (ref "HLR7") (pin "2") (pinfunction "2_2") (pintype "passive"))
      (node (ref "IC4") (pin "13") (pinfunction "-IND_13") (pintype "input"))
    )
    (net (code "20") (name "/-HP{slash}LP_AMP5") (class "Default")
      (node (ref "H/LC3") (pin "2") (pinfunction "2_2") (pintype "passive"))
      (node (ref "IC4") (pin "9") (pinfunction "-INC_9") (pintype "input"))
      (node (ref "X30") (pin "2") (pinfunction "S_2") (pintype "passive"))
    )
    (net (code "21") (name "/-HP{slash}LP_AMP6") (class "Default")
      (node (ref "H/LC4") (pin "2") (pinfunction "2_2") (pintype "passive"))
      (node (ref "IC5") (pin "2") (pinfunction "-INA_2") (pintype "input"))
      (node (ref "X32") (pin "2") (pinfunction "S_2") (pintype "passive"))
    )
    (net (code "22") (name "/-HP{slash}LP_AMP7") (class "Default")
      (node (ref "HLR10") (pin "1") (pinfunction "1_1") (pintype "passive"))
      (node (ref "HLR11") (pin "2") (pinfunction "2_2") (pintype "passive"))
      (node (ref "HLR9") (pin "2") (pinfunction "2_2") (pintype "passive"))
      (node (ref "IC5") (pin "6") (pinfunction "-INB_6") (pintype "input"))
    )
    (net (code "23") (name "/-HP{slash}LP_AMP8") (class "Default")
      (node (ref "H/LC5") (pin "2") (pinfunction "2_2") (pintype "passive"))
      (node (ref "IC5") (pin "13") (pinfunction "-IND_13") (pintype "input"))
      (node (ref "X26") (pin "2") (pinfunction "S_2") (pintype "passive"))
    )
    (net (code "24") (name "/-HP{slash}LP_AMP9") (class "Default")
      (node (ref "H/LC6") (pin "2") (pinfunction "2_2") (pintype "passive"))
      (node (ref "IC5") (pin "9") (pinfunction "-INC_9") (pintype "input"))
      (node (ref "X28") (pin "2") (pinfunction "S_2") (pintype "passive"))
    )
    (net (code "25") (name "/-NOTCH") (class "Default")
      (node (ref "IC1") (pin "2") (pinfunction "-INA_2") (pintype "input"))
      (node (ref "NR3") (pin "1") (pinfunction "1_1") (pintype "passive"))
      (node (ref "NR4") (pin "2") (pinfunction "2_2") (pintype "passive"))
    )
    (net (code "26") (name "/BP2_BUFFER_IN") (class "Default")
      (node (ref "B2C1") (pin "1") (pinfunction "1_1") (pintype "passive"))
      (node (ref "IC1") (pin "12") (pinfunction "+IND_12") (pintype "input"))
      (node (ref "X7") (pin "1") (pinfunction "S_1") (pintype "passive"))
    )
    (net (code "27") (name "/BP2_BUFFER_OUT") (class "Default")
      (node (ref "IC1") (pin "13") (pinfunction "-IND_13") (pintype "input"))
      (node (ref "IC1") (pin "14") (pinfunction "OUTD_14") (pintype "output"))
      (node (ref "X4") (pin "2") (pinfunction "S_2") (pintype "passive"))
    )
    (net (code "28") (name "/BP2_IN") (class "Default")
      (node (ref "B2C1") (pin "2") (pinfunction "2_2") (pintype "passive"))
      (node (ref "SYS_IN") (pin "1") (pinfunction "A4_1") (pintype "bidirectional"))
    )
    (net (code "29") (name "/BP2_OUT") (class "Default")
      (node (ref "B2C2") (pin "1") (pinfunction "1_1") (pintype "passive"))
      (node (ref "SYS_OUT") (pin "1") (pinfunction "A4_1") (pintype "bidirectional"))
      (node (ref "X8") (pin "1") (pinfunction "S_1") (pintype "passive"))
    )
    (net (code "30") (name "/BP2_POT1_IN") (class "Default")
      (node (ref "POTA") (pin "17") (pinfunction "VW1/RW1_17") (pintype "passive"))
      (node (ref "X7") (pin "2") (pinfunction "S_2") (pintype "passive"))
    )
    (net (code "31") (name "/BP2_POT1_OUT") (class "Default")
      (node (ref "POTA") (pin "16") (pinfunction "VH1/RH1_16") (pintype "passive"))
      (node (ref "X3") (pin "1") (pinfunction "S_1") (pintype "passive"))
    )
    (net (code "32") (name "/BP2_POT2_IN") (class "Default")
      (node (ref "POTA") (pin "21") (pinfunction "VH2/RH2_21") (pintype "passive"))
      (node (ref "X4") (pin "1") (pinfunction "S_1") (pintype "passive"))
    )
    (net (code "33") (name "/BP2_POT2_OUT") (class "Default")
      (node (ref "POTA") (pin "20") (pinfunction "VW2/RW2_20") (pintype "passive"))
      (node (ref "X8") (pin "2") (pinfunction "S_2") (pintype "passive"))
    )
    (net (code "34") (name "/BP6_AMP1_OUT") (class "Default")
      (node (ref "B6R3") (pin "1") (pinfunction "1_1") (pintype "passive"))
      (node (ref "IC2") (pin "1") (pinfunction "OUTA_1") (pintype "output"))
      (node (ref "X9") (pin "1") (pinfunction "S_1") (pintype "passive"))
    )
    (net (code "35") (name "/BP6_AMP2_OUT") (class "Default")
      (node (ref "B6C1") (pin "1") (pinfunction "1_1") (pintype "passive"))
      (node (ref "B6R4") (pin "1") (pinfunction "1_1") (pintype "passive"))
      (node (ref "IC2") (pin "7") (pinfunction "OUTB_7") (pintype "output"))
      (node (ref "X11") (pin "1") (pinfunction "S_1") (pintype "passive"))
    )
    (net (code "36") (name "/BP6_AMP3_OUT") (class "Default")
      (node (ref "B6C2") (pin "1") (pinfunction "1_1") (pintype "passive"))
      (node (ref "B6R1") (pin "1") (pinfunction "1_1") (pintype "passive"))
      (node (ref "IC2") (pin "14") (pinfunction "OUTD_14") (pintype "output"))
      (node (ref "X17") (pin "1") (pinfunction "S_1") (pintype "passive"))
    )
    (net (code "37") (name "/BP6_AMP4_OUT") (class "Default")
      (node (ref "B6R7") (pin "1") (pinfunction "1_1") (pintype "passive"))
      (node (ref "IC3") (pin "1") (pinfunction "OUTA_1") (pintype "output"))
      (node (ref "X13") (pin "1") (pinfunction "S_1") (pintype "passive"))
    )
    (net (code "38") (name "/BP6_AMP5_OUT") (class "Default")
      (node (ref "B6C4") (pin "1") (pinfunction "1_1") (pintype "passive"))
      (node (ref "B6R8") (pin "1") (pinfunction "1_1") (pintype "passive"))
      (node (ref "IC3") (pin "7") (pinfunction "OUTB_7") (pintype "output"))
      (node (ref "X15") (pin "1") (pinfunction "S_1") (pintype "passive"))
    )
    (net (code "39") (name "/BP6_AMP6_OUT") (class "Default")
      (node (ref "B6C5") (pin "1") (pinfunction "1_1") (pintype "passive"))
      (node (ref "B6C6") (pin "1") (pinfunction "1_1") (pintype "passive"))
      (node (ref "B6R5") (pin "1") (pinfunction "1_1") (pintype "passive"))
      (node (ref "IC3") (pin "14") (pinfunction "OUTD_14") (pintype "output"))
    )
    (net (code "40") (name "/BP6_BUFFER") (class "Default")
      (node (ref "B6C3") (pin "1") (pinfunction "1_1") (pintype "passive"))
      (node (ref "IC2") (pin "10") (pinfunction "+INC_10") (pintype "input"))
      (node (ref "X18") (pin "2") (pinfunction "S_2") (pintype "passive"))
    )
    (net (code "41") (name "/BP6_BUFFER_OUT") (class "Default")
      (node (ref "B6R6") (pin "2") (pinfunction "2_2") (pintype "passive"))
      (node (ref "IC2") (pin "8") (pinfunction "OUTC_8") (pintype "output"))
      (node (ref "IC2") (pin "9") (pinfunction "-INC_9") (pintype "input"))
    )
    (net (code "42") (name "/BP6_IN") (class "Default")
      (node (ref "B6R2") (pin "2") (pinfunction "2_2") (pintype "passive"))
      (node (ref "SYS_IN") (pin "5") (pinfunction "A5_5") (pintype "bidirectional"))
    )
    (net (code "43") (name "/BP6_OUT") (class "Default")
      (node (ref "B6C6") (pin "2") (pinfunction "2_2") (pintype "passive"))
      (node (ref "SYS_OUT") (pin "5") (pinfunction "A5_5") (pintype "bidirectional"))
      (node (ref "X19") (pin "2") (pinfunction "S_2") (pintype "passive"))
    )
    (net (code "44") (name "/BP6_POT1_IN") (class "Default")
      (node (ref "POTB") (pin "3") (pinfunction "VW3/RW3_3") (pintype "passive"))
      (node (ref "X9") (pin "2") (pinfunction "S_2") (pintype "passive"))
    )
    (net (code "45") (name "/BP6_POT1_OUT") (class "Default")
      (node (ref "POTB") (pin "4") (pinfunction "VH3/RH3_4") (pintype "passive"))
      (node (ref "X10") (pin "1") (pinfunction "S_1") (pintype "passive"))
    )
    (net (code "46") (name "/BP6_POT2_IN") (class "Default")
      (node (ref "POTB") (pin "9") (pinfunction "VH0/RH0_9") (pintype "passive"))
      (node (ref "X11") (pin "2") (pinfunction "S_2") (pintype "passive"))
    )
    (net (code "47") (name "/BP6_POT2_OUT") (class "Default")
      (node (ref "POTB") (pin "10") (pinfunction "VW0/RW0_10") (pintype "passive"))
      (node (ref "X12") (pin "1") (pinfunction "S_1") (pintype "passive"))
    )
    (net (code "48") (name "/BP6_POT3_IN") (class "Default")
      (node (ref "POTB") (pin "21") (pinfunction "VH2/RH2_21") (pintype "passive"))
      (node (ref "X17") (pin "2") (pinfunction "S_2") (pintype "passive"))
    )
    (net (code "49") (name "/BP6_POT3_OUT") (class "Default")
      (node (ref "POTB") (pin "20") (pinfunction "VW2/RW2_20") (pintype "passive"))
      (node (ref "X18") (pin "1") (pinfunction "S_1") (pintype "passive"))
    )
    (net (code "50") (name "/BP6_POT4_IN") (class "Default")
      (node (ref "POTB") (pin "16") (pinfunction "VH1/RH1_16") (pintype "passive"))
      (node (ref "X13") (pin "2") (pinfunction "S_2") (pintype "passive"))
    )
    (net (code "51") (name "/BP6_POT4_OUT") (class "Default")
      (node (ref "X14") (pin "1") (pinfunction "S_1") (pintype "passive"))
    )
    (net (code "52") (name "/BP6_POT5_IN") (class "Default")
      (node (ref "C") (pin "3") (pinfunction "VW3/RW3_3") (pintype "passive"))
      (node (ref "X15") (pin "2") (pinfunction "S_2") (pintype "passive"))
    )
    (net (code "53") (name "/BP6_POT5_OUT") (class "Default")
      (node (ref "C") (pin "4") (pinfunction "VH3/RH3_4") (pintype "passive"))
      (node (ref "X16") (pin "1") (pinfunction "S_1") (pintype "passive"))
    )
    (net (code "54") (name "/BP6_POT6_IN") (class "Default")
      (node (ref "C") (pin "9") (pinfunction "VH0/RH0_9") (pintype "passive"))
      (node (ref "X19") (pin "1") (pinfunction "S_1") (pintype "passive"))
    )
    (net (code "55") (name "/BP6_POT6_OUT") (class "Default")
      (node (ref "C") (pin "10") (pinfunction "VW0/RW0_10") (pintype "passive"))
      (node (ref "X20") (pin "2") (pinfunction "S_2") (pintype "passive"))
    )
    (net (code "56") (name "/BUFFER1_IN") (class "Default")
      (node (ref "IC1") (pin "5") (pinfunction "+INB_5") (pintype "input"))
    )
    (net (code "57") (name "/BUFFER2_IN") (class "Default")
      (node (ref "IC1") (pin "10") (pinfunction "+INC_10") (pintype "input"))
    )
    (net (code "58") (name "/GND") (class "Default")
      (node (ref "B2C2") (pin "2") (pinfunction "2_2") (pintype "passive"))
      (node (ref "B6C3") (pin "2") (pinfunction "2_2") (pintype "passive"))
      (node (ref "B6Q1") (pin "2") (pinfunction "2_2") (pintype "passive"))
      (node (ref "B6Q2") (pin "2") (pinfunction "2_2") (pintype "passive"))
      (node (ref "C") (pin "18") (pinfunction "VSS_18") (pintype "power_in"))
      (node (ref "D") (pin "18") (pinfunction "VSS_18") (pintype "power_in"))
      (node (ref "HP/LP_TOGGLE") (pin "8") (pinfunction "GND_8") (pintype "power_in"))
      (node (ref "HQ1") (pin "2") (pinfunction "2_2") (pintype "passive"))
      (node (ref "HQ2") (pin "2") (pinfunction "2_2") (pintype "passive"))
      (node (ref "HQ3") (pin "2") (pinfunction "2_2") (pintype "passive"))
      (node (ref "IC2") (pin "12") (pinfunction "+IND_12") (pintype "input"))
      (node (ref "IC2") (pin "5") (pinfunction "+INB_5") (pintype "input"))
      (node (ref "IC3") (pin "12") (pinfunction "+IND_12") (pintype "input"))
      (node (ref "IC3") (pin "5") (pinfunction "+INB_5") (pintype "input"))
      (node (ref "IC4") (pin "10") (pinfunction "+INC_10") (pintype "input"))
      (node (ref "IC4") (pin "3") (pinfunction "+INA_3") (pintype "input"))
      (node (ref "IC4") (pin "5") (pinfunction "+INB_5") (pintype "input"))
      (node (ref "IC5") (pin "10") (pinfunction "+INC_10") (pintype "input"))
      (node (ref "IC5") (pin "12") (pinfunction "+IND_12") (pintype "input"))
      (node (ref "IC5") (pin "3") (pinfunction "+INA_3") (pintype "input"))
      (node (ref "LPC") (pin "1") (pinfunction "1_1") (pintype "passive"))
      (node (ref "NR2") (pin "1") (pinfunction "1_1") (pintype "passive"))
      (node (ref "PA0") (pin "1") (pinfunction "1_1") (pintype "passive"))
      (node (ref "PA1") (pin "2") (pinfunction "2_2") (pintype "passive"))
      (node (ref "PA2") (pin "1") (pinfunction "1_1") (pintype "passive"))
      (node (ref "PA3") (pin "2") (pinfunction "2_2") (pintype "passive"))
      (node (ref "PB1") (pin "2") (pinfunction "2_2") (pintype "passive"))
      (node (ref "PB2") (pin "1") (pinfunction "1_1") (pintype "passive"))
      (node (ref "PB3") (pin "2") (pinfunction "2_2") (pintype "passive"))
      (node (ref "PC0") (pin "1") (pinfunction "1_1") (pintype "passive"))
      (node (ref "PC2") (pin "1") (pinfunction "1_1") (pintype "passive"))
      (node (ref "PC3") (pin "2") (pinfunction "2_2") (pintype "passive"))
      (node (ref "PD2") (pin "1") (pinfunction "1_1") (pintype "passive"))
      (node (ref "PD3") (pin "2") (pinfunction "2_2") (pintype "passive"))
      (node (ref "POTA") (pin "18") (pinfunction "VSS_18") (pintype "power_in"))
      (node (ref "POTB") (pin "18") (pinfunction "VSS_18") (pintype "power_in"))
      (node (ref "RE") (pin "2") (pinfunction "2_2") (pintype "passive"))
      (node (ref "RS0") (pin "2") (pinfunction "2_2") (pintype "passive"))
      (node (ref "RS1") (pin "2") (pinfunction "2_2") (pintype "passive"))
      (node (ref "RS2") (pin "2") (pinfunction "2_2") (pintype "passive"))
      (node (ref "S0-3R") (pin "2") (pinfunction "2_2") (pintype "passive"))
      (node (ref "SV1") (pin "4") (pinfunction "4_4") (pintype "passive"))
      (node (ref "SV1") (pin "6") (pinfunction "6_6") (pintype "passive"))
      (node (ref "SYS_IN") (pin "8") (pinfunction "GND_8") (pintype "power_in"))
      (node (ref "SYS_OUT") (pin "8") (pinfunction "GND_8") (pintype "power_in"))
      (node (ref "X1") (pin "2") (pinfunction "S_2") (pintype "passive"))
      (node (ref "X20") (pin "1") (pinfunction "S_1") (pintype "passive"))
      (node (ref "X3") (pin "2") (pinfunction "S_2") (pintype "passive"))
      (node (ref "X33") (pin "2") (pinfunction "S_2") (pintype "passive"))
      (node (ref "X34") (pin "2") (pinfunction "S_2") (pintype "passive"))
    )
    (net (code "59") (name "/HP1_IN") (class "Default")
      (node (ref "HPC") (pin "1") (pinfunction "1_1") (pintype "passive"))
      (node (ref "SYS_IN") (pin "15") (pinfunction "A2_15") (pintype "bidirectional"))
    )
    (net (code "60") (name "/HP1_OUT") (class "Default")
      (node (ref "HPC") (pin "2") (pinfunction "2_2") (pintype "passive"))
      (node (ref "SYS_OUT") (pin "15") (pinfunction "A2_15") (pintype "bidirectional"))
      (node (ref "X2") (pin "1") (pinfunction "S_1") (pintype "passive"))
    )
    (net (code "61") (name "/HP1_POT_IN") (class "Default")
      (node (ref "POTA") (pin "3") (pinfunction "VW3/RW3_3") (pintype "passive"))
      (node (ref "X2") (pin "2") (pinfunction "S_2") (pintype "passive"))
    )
    (net (code "62") (name "/HP1_POT_OUT") (class "Default")
      (node (ref "POTA") (pin "4") (pinfunction "VH3/RH3_4") (pintype "passive"))
      (node (ref "X1") (pin "1") (pinfunction "S_1") (pintype "passive"))
    )
    (net (code "63") (name "/HP{slash}LP_AMP2_OUT") (class "Default")
      (node (ref "H/LC1") (pin "1") (pinfunction "1_1") (pintype "passive"))
      (node (ref "HLR4") (pin "1") (pinfunction "1_1") (pintype "passive"))
      (node (ref "IC4") (pin "1") (pinfunction "OUTA_1") (pintype "output"))
      (node (ref "X23") (pin "1") (pinfunction "S_1") (pintype "passive"))
    )
    (net (code "64") (name "/HP{slash}LP_AMP5_OUT") (class "Default")
      (node (ref "H/LC3") (pin "1") (pinfunction "1_1") (pintype "passive"))
      (node (ref "HLR8") (pin "1") (pinfunction "1_1") (pintype "passive"))
      (node (ref "IC4") (pin "8") (pinfunction "OUTC_8") (pintype "output"))
      (node (ref "X31") (pin "1") (pinfunction "S_1") (pintype "passive"))
    )
    (net (code "65") (name "/HP{slash}LP_AMP8_OUT") (class "Default")
      (node (ref "H/LC5") (pin "1") (pinfunction "1_1") (pintype "passive"))
      (node (ref "HLR12") (pin "1") (pinfunction "1_1") (pintype "passive"))
      (node (ref "IC5") (pin "14") (pinfunction "OUTD_14") (pintype "output"))
      (node (ref "X27") (pin "1") (pinfunction "S_1") (pintype "passive"))
    )
    (net (code "66") (name "/HP{slash}LP_HP_OUT1") (class "Default")
      (node (ref "HLR3") (pin "1") (pinfunction "1_1") (pintype "passive"))
      (node (ref "HP/LP_TOGGLE") (pin "12") (pinfunction "A0_12") (pintype "passive"))
      (node (ref "IC3") (pin "8") (pinfunction "OUTC_8") (pintype "output"))
      (node (ref "X21") (pin "1") (pinfunction "S_1") (pintype "passive"))
    )
    (net (code "67") (name "/HP{slash}LP_HP_OUT2") (class "Default")
      (node (ref "HLR7") (pin "1") (pinfunction "1_1") (pintype "passive"))
      (node (ref "HP/LP_TOGGLE") (pin "2") (pinfunction "B0_2") (pintype "passive"))
      (node (ref "IC4") (pin "14") (pinfunction "OUTD_14") (pintype "output"))
      (node (ref "X29") (pin "1") (pinfunction "S_1") (pintype "passive"))
    )
    (net (code "68") (name "/HP{slash}LP_HP_OUT3") (class "Default")
      (node (ref "HLR11") (pin "1") (pinfunction "1_1") (pintype "passive"))
      (node (ref "HP/LP_TOGGLE") (pin "5") (pinfunction "C0_5") (pintype "passive"))
      (node (ref "IC5") (pin "7") (pinfunction "OUTB_7") (pintype "output"))
      (node (ref "X25") (pin "1") (pinfunction "S_1") (pintype "passive"))
    )
    (net (code "69") (name "/HP{slash}LP_IN1") (class "Default")
      (node (ref "HLR1") (pin "2") (pinfunction "2_2") (pintype "passive"))
      (node (ref "SYS_IN") (pin "2") (pinfunction "A6_2") (pintype "bidirectional"))
    )
    (net (code "70") (name "/HP{slash}LP_IN2") (class "Default")
      (node (ref "HLR6") (pin "2") (pinfunction "2_2") (pintype "passive"))
      (node (ref "HP/LP_TOGGLE") (pin "14") (pinfunction "AN_14") (pintype "passive"))
    )
    (net (code "71") (name "/HP{slash}LP_IN3") (class "Default")
      (node (ref "HLR10") (pin "2") (pinfunction "2_2") (pintype "passive"))
      (node (ref "HP/LP_TOGGLE") (pin "15") (pinfunction "BN_15") (pintype "passive"))
    )
    (net (code "72") (name "/HP{slash}LP_LP_OUT1") (class "Default")
      (node (ref "H/LC2") (pin "1") (pinfunction "1_1") (pintype "passive"))
      (node (ref "HLR2") (pin "1") (pinfunction "1_1") (pintype "passive"))
      (node (ref "HP/LP_TOGGLE") (pin "13") (pinfunction "A1_13") (pintype "passive"))
      (node (ref "IC4") (pin "7") (pinfunction "OUTB_7") (pintype "output"))
    )
    (net (code "73") (name "/HP{slash}LP_LP_OUT2") (class "Default")
      (node (ref "H/LC4") (pin "1") (pinfunction "1_1") (pintype "passive"))
      (node (ref "HLR5") (pin "1") (pinfunction "1_1") (pintype "passive"))
      (node (ref "HP/LP_TOGGLE") (pin "1") (pinfunction "B1_1") (pintype "passive"))
      (node (ref "IC5") (pin "1") (pinfunction "OUTA_1") (pintype "output"))
    )
    (net (code "74") (name "/HP{slash}LP_LP_OUT3") (class "Default")
      (node (ref "H/LC6") (pin "1") (pinfunction "1_1") (pintype "passive"))
      (node (ref "HLR9") (pin "1") (pinfunction "1_1") (pintype "passive"))
      (node (ref "HP/LP_TOGGLE") (pin "3") (pinfunction "C1_3") (pintype "passive"))
      (node (ref "IC5") (pin "8") (pinfunction "OUTC_8") (pintype "output"))
    )
    (net (code "75") (name "/HP{slash}LP_OUT") (class "Default")
      (node (ref "HP/LP_TOGGLE") (pin "4") (pinfunction "CN_4") (pintype "passive"))
      (node (ref "SYS_OUT") (pin "2") (pinfunction "A6_2") (pintype "bidirectional"))
    )
    (net (code "76") (name "/HP{slash}LP_POT1_IN") (class "Default")
      (node (ref "C") (pin "21") (pinfunction "VH2/RH2_21") (pintype "passive"))
      (node (ref "X21") (pin "2") (pinfunction "S_2") (pintype "passive"))
    )
    (net (code "77") (name "/HP{slash}LP_POT1_OUT") (class "Default")
      (node (ref "C") (pin "20") (pinfunction "VW2/RW2_20") (pintype "passive"))
      (node (ref "X22") (pin "1") (pinfunction "S_1") (pintype "passive"))
    )
    (net (code "78") (name "/HP{slash}LP_POT2_IN") (class "Default")
      (node (ref "C") (pin "17") (pinfunction "VW1/RW1_17") (pintype "passive"))
      (node (ref "X23") (pin "2") (pinfunction "S_2") (pintype "passive"))
    )
    (net (code "79") (name "/HP{slash}LP_POT2_OUT") (class "Default")
      (node (ref "C") (pin "16") (pinfunction "VH1/RH1_16") (pintype "passive"))
      (node (ref "X24") (pin "1") (pinfunction "S_1") (pintype "passive"))
    )
    (net (code "80") (name "/HP{slash}LP_POT3_IN") (class "Default")
      (node (ref "D") (pin "4") (pinfunction "VH3/RH3_4") (pintype "passive"))
      (node (ref "X29") (pin "2") (pinfunction "S_2") (pintype "passive"))
    )
    (net (code "81") (name "/HP{slash}LP_POT3_OUT") (class "Default")
      (node (ref "D") (pin "5") (pinfunction "VL3/RL3_5") (pintype "passive"))
      (node (ref "X30") (pin "1") (pinfunction "S_1") (pintype "passive"))
    )
    (net (code "82") (name "/HP{slash}LP_POT4_IN") (class "Default")
      (node (ref "D") (pin "21") (pinfunction "VH2/RH2_21") (pintype "passive"))
      (node (ref "D") (pin "9") (pinfunction "VH0/RH0_9") (pintype "passive"))
      (node (ref "X31") (pin "2") (pinfunction "S_2") (pintype "passive"))
    )
    (net (code "83") (name "/HP{slash}LP_POT4_OUT") (class "Default")
      (node (ref "D") (pin "10") (pinfunction "VW0/RW0_10") (pintype "passive"))
      (node (ref "D") (pin "20") (pinfunction "VW2/RW2_20") (pintype "passive"))
      (node (ref "X32") (pin "1") (pinfunction "S_1") (pintype "passive"))
    )
    (net (code "84") (name "/HP{slash}LP_POT5_IN") (class "Default")
      (node (ref "X25") (pin "2") (pinfunction "S_2") (pintype "passive"))
    )
    (net (code "85") (name "/HP{slash}LP_POT5_OUT") (class "Default")
      (node (ref "X26") (pin "1") (pinfunction "S_1") (pintype "passive"))
    )
    (net (code "86") (name "/HP{slash}LP_POT6_IN") (class "Default")
      (node (ref "D") (pin "17") (pinfunction "VW1/RW1_17") (pintype "passive"))
      (node (ref "X27") (pin "2") (pinfunction "S_2") (pintype "passive"))
    )
    (net (code "87") (name "/HP{slash}LP_POT6_OUT") (class "Default")
      (node (ref "D") (pin "16") (pinfunction "VH1/RH1_16") (pintype "passive"))
      (node (ref "X28") (pin "1") (pinfunction "S_1") (pintype "passive"))
    )
    (net (code "88") (name "/HP{slash}LP_TOGGLE") (class "Default")
      (node (ref "HP/LP_TOGGLE") (pin "10") (pinfunction "S1_10") (pintype "input"))
      (node (ref "HP/LP_TOGGLE") (pin "11") (pinfunction "S0_11") (pintype "input"))
      (node (ref "HP/LP_TOGGLE") (pin "9") (pinfunction "S2_9") (pintype "input"))
      (node (ref "S0-3R") (pin "1") (pinfunction "1_1") (pintype "passive"))
      (node (ref "SV1") (pin "8") (pinfunction "8_8") (pintype "passive"))
    )
    (net (code "89") (name "/LP1_IN") (class "Default")
      (node (ref "SYS_IN") (pin "12") (pinfunction "A3_12") (pintype "bidirectional"))
      (node (ref "X5") (pin "2") (pinfunction "S_2") (pintype "passive"))
    )
    (net (code "90") (name "/LP1_OUT") (class "Default")
      (node (ref "LPC") (pin "2") (pinfunction "2_2") (pintype "passive"))
      (node (ref "SYS_OUT") (pin "12") (pinfunction "A3_12") (pintype "bidirectional"))
      (node (ref "X6") (pin "1") (pinfunction "S_1") (pintype "passive"))
    )
    (net (code "91") (name "/LP1_POT_IN") (class "Default")
      (node (ref "POTA") (pin "9") (pinfunction "VH0/RH0_9") (pintype "passive"))
      (node (ref "X5") (pin "1") (pinfunction "S_1") (pintype "passive"))
    )
    (net (code "92") (name "/LP1_POT_OUT") (class "Default")
      (node (ref "POTA") (pin "10") (pinfunction "VW0/RW0_10") (pintype "passive"))
      (node (ref "X6") (pin "2") (pinfunction "S_2") (pintype "passive"))
    )
    (net (code "93") (name "/NOTCH_AMP_OUT") (class "Default")
      (node (ref "IC1") (pin "1") (pinfunction "OUTA_1") (pintype "output"))
      (node (ref "NC2") (pin "1") (pinfunction "1_1") (pintype "passive"))
      (node (ref "NR4") (pin "1") (pinfunction "1_1") (pintype "passive"))
    )
    (net (code "94") (name "/NOTCH_IN") (class "Default")
      (node (ref "NC1") (pin "1") (pinfunction "1_1") (pintype "passive"))
      (node (ref "NR1") (pin "2") (pinfunction "2_2") (pintype "passive"))
      (node (ref "NR3") (pin "2") (pinfunction "2_2") (pintype "passive"))
      (node (ref "SYS_IN") (pin "14") (pinfunction "A1_14") (pintype "bidirectional"))
    )
    (net (code "95") (name "/NOTCH_OUT") (class "Default")
      (node (ref "NC2") (pin "2") (pinfunction "2_2") (pintype "passive"))
      (node (ref "NR1") (pin "1") (pinfunction "1_1") (pintype "passive"))
      (node (ref "SYS_OUT") (pin "14") (pinfunction "A1_14") (pintype "bidirectional"))
    )
    (net (code "96") (name "/PASS") (class "Default")
      (node (ref "SYS_IN") (pin "13") (pinfunction "A0_13") (pintype "bidirectional"))
      (node (ref "SYS_OUT") (pin "13") (pinfunction "A0_13") (pintype "bidirectional"))
    )
    (net (code "97") (name "/SCL") (class "Default")
      (node (ref "C") (pin "23") (pinfunction "SCL_23") (pintype "passive"))
      (node (ref "D") (pin "23") (pinfunction "SCL_23") (pintype "passive"))
      (node (ref "POTA") (pin "23") (pinfunction "SCL_23") (pintype "passive"))
      (node (ref "POTB") (pin "23") (pinfunction "SCL_23") (pintype "passive"))
      (node (ref "SCLR") (pin "2") (pinfunction "2_2") (pintype "passive"))
      (node (ref "SV1") (pin "12") (pinfunction "12_12") (pintype "passive"))
    )
    (net (code "98") (name "/SDA") (class "Default")
      (node (ref "C") (pin "13") (pinfunction "SDA_13") (pintype "passive"))
      (node (ref "D") (pin "13") (pinfunction "SDA_13") (pintype "passive"))
      (node (ref "POTA") (pin "13") (pinfunction "SDA_13") (pintype "passive"))
      (node (ref "POTB") (pin "13") (pinfunction "SDA_13") (pintype "passive"))
      (node (ref "SDAR") (pin "2") (pinfunction "2_2") (pintype "passive"))
      (node (ref "SV1") (pin "2") (pinfunction "2_2") (pintype "passive"))
    )
    (net (code "99") (name "/SYSTEM_0") (class "Default")
      (node (ref "RS0") (pin "1") (pinfunction "1_1") (pintype "passive"))
      (node (ref "SV1") (pin "9") (pinfunction "9_9") (pintype "passive"))
      (node (ref "SYS_IN") (pin "11") (pinfunction "S0_11") (pintype "output"))
      (node (ref "SYS_OUT") (pin "11") (pinfunction "S0_11") (pintype "output"))
    )
    (net (code "100") (name "/SYSTEM_1") (class "Default")
      (node (ref "RS1") (pin "1") (pinfunction "1_1") (pintype "passive"))
      (node (ref "SV1") (pin "7") (pinfunction "7_7") (pintype "passive"))
      (node (ref "SYS_IN") (pin "10") (pinfunction "S1_10") (pintype "output"))
      (node (ref "SYS_OUT") (pin "10") (pinfunction "S1_10") (pintype "output"))
    )
    (net (code "101") (name "/SYSTEM_2") (class "Default")
      (node (ref "RS2") (pin "1") (pinfunction "1_1") (pintype "passive"))
      (node (ref "SV1") (pin "5") (pinfunction "5_5") (pintype "passive"))
      (node (ref "SYS_IN") (pin "9") (pinfunction "S2_9") (pintype "output"))
      (node (ref "SYS_OUT") (pin "9") (pinfunction "S2_9") (pintype "output"))
    )
    (net (code "102") (name "/SYSTEM_E") (class "Default")
      (node (ref "HP/LP_TOGGLE") (pin "6") (pinfunction "~{E}_6") (pintype "passive"))
      (node (ref "RE") (pin "1") (pinfunction "1_1") (pintype "passive"))
      (node (ref "SV1") (pin "3") (pinfunction "3_3") (pintype "passive"))
      (node (ref "SYS_IN") (pin "6") (pinfunction "~{E}_6") (pintype "input"))
      (node (ref "SYS_OUT") (pin "6") (pinfunction "~{E}_6") (pintype "input"))
    )
    (net (code "103") (name "/SYSTEM_IN") (class "Default")
      (node (ref "IC1") (pin "8") (pinfunction "OUTC_8") (pintype "output"))
      (node (ref "IC1") (pin "9") (pinfunction "-INC_9") (pintype "input"))
      (node (ref "SYS_IN") (pin "3") (pinfunction "A_3") (pintype "bidirectional"))
      (node (ref "X33") (pin "1") (pinfunction "S_1") (pintype "passive"))
    )
    (net (code "104") (name "/SYSTEM_OUT") (class "Default")
      (node (ref "IC1") (pin "6") (pinfunction "-INB_6") (pintype "input"))
      (node (ref "IC1") (pin "7") (pinfunction "OUTB_7") (pintype "output"))
      (node (ref "SYS_OUT") (pin "3") (pinfunction "A_3") (pintype "bidirectional"))
      (node (ref "X34") (pin "1") (pinfunction "S_1") (pintype "passive"))
    )
    (net (code "105") (name "Net-(C-A0)") (class "Default")
      (node (ref "C") (pin "2") (pinfunction "A0_2") (pintype "passive"))
      (node (ref "PC0") (pin "2") (pinfunction "2_2") (pintype "passive"))
    )
    (net (code "106") (name "Net-(C-A1)") (class "Default")
      (node (ref "C") (pin "14") (pinfunction "A1_14") (pintype "passive"))
      (node (ref "PC1") (pin "1") (pinfunction "1_1") (pintype "passive"))
    )
    (net (code "107") (name "Net-(C-A2)") (class "Default")
      (node (ref "C") (pin "11") (pinfunction "A2_11") (pintype "passive"))
      (node (ref "PC2") (pin "2") (pinfunction "2_2") (pintype "passive"))
    )
    (net (code "108") (name "Net-(C-A3)") (class "Default")
      (node (ref "C") (pin "24") (pinfunction "A3_24") (pintype "passive"))
      (node (ref "PC3") (pin "1") (pinfunction "1_1") (pintype "passive"))
    )
    (net (code "109") (name "Net-(D-A0)") (class "Default")
      (node (ref "D") (pin "2") (pinfunction "A0_2") (pintype "passive"))
      (node (ref "PD0") (pin "2") (pinfunction "2_2") (pintype "passive"))
    )
    (net (code "110") (name "Net-(D-A1)") (class "Default")
      (node (ref "D") (pin "14") (pinfunction "A1_14") (pintype "passive"))
      (node (ref "PD1") (pin "1") (pinfunction "1_1") (pintype "passive"))
    )
    (net (code "111") (name "Net-(D-A2)") (class "Default")
      (node (ref "D") (pin "11") (pinfunction "A2_11") (pintype "passive"))
      (node (ref "PD2") (pin "2") (pinfunction "2_2") (pintype "passive"))
    )
    (net (code "112") (name "Net-(D-A3)") (class "Default")
      (node (ref "D") (pin "24") (pinfunction "A3_24") (pintype "passive"))
      (node (ref "PD3") (pin "1") (pinfunction "1_1") (pintype "passive"))
    )
    (net (code "113") (name "Net-(POTA-A0)") (class "Default")
      (node (ref "PA0") (pin "2") (pinfunction "2_2") (pintype "passive"))
      (node (ref "POTA") (pin "2") (pinfunction "A0_2") (pintype "passive"))
    )
    (net (code "114") (name "Net-(POTA-A1)") (class "Default")
      (node (ref "PA1") (pin "1") (pinfunction "1_1") (pintype "passive"))
      (node (ref "POTA") (pin "14") (pinfunction "A1_14") (pintype "passive"))
    )
    (net (code "115") (name "Net-(POTA-A2)") (class "Default")
      (node (ref "PA2") (pin "2") (pinfunction "2_2") (pintype "passive"))
      (node (ref "POTA") (pin "11") (pinfunction "A2_11") (pintype "passive"))
    )
    (net (code "116") (name "Net-(POTA-A3)") (class "Default")
      (node (ref "PA3") (pin "1") (pinfunction "1_1") (pintype "passive"))
      (node (ref "POTA") (pin "24") (pinfunction "A3_24") (pintype "passive"))
    )
    (net (code "117") (name "Net-(POTB-A0)") (class "Default")
      (node (ref "PB0") (pin "2") (pinfunction "2_2") (pintype "passive"))
      (node (ref "POTB") (pin "2") (pinfunction "A0_2") (pintype "passive"))
    )
    (net (code "118") (name "Net-(POTB-A1)") (class "Default")
      (node (ref "PB1") (pin "1") (pinfunction "1_1") (pintype "passive"))
      (node (ref "POTB") (pin "14") (pinfunction "A1_14") (pintype "passive"))
    )
    (net (code "119") (name "Net-(POTB-A2)") (class "Default")
      (node (ref "PB2") (pin "2") (pinfunction "2_2") (pintype "passive"))
      (node (ref "POTB") (pin "11") (pinfunction "A2_11") (pintype "passive"))
    )
    (net (code "120") (name "Net-(POTB-A3)") (class "Default")
      (node (ref "PB3") (pin "1") (pinfunction "1_1") (pintype "passive"))
      (node (ref "POTB") (pin "24") (pinfunction "A3_24") (pintype "passive"))
    )
    (net (code "121") (name "unconnected-(C-NC-Pad1)") (class "Default")
      (node (ref "C") (pin "1") (pinfunction "NC_1") (pintype "no_connect"))
    )
    (net (code "122") (name "unconnected-(C-VL0{slash}RL0-Pad8)") (class "Default")
      (node (ref "C") (pin "8") (pinfunction "VL0/RL0_8") (pintype "passive"))
    )
    (net (code "123") (name "unconnected-(C-VL1{slash}RW1-Pad15)") (class "Default")
      (node (ref "C") (pin "15") (pinfunction "VL1/RW1_15") (pintype "passive"))
    )
    (net (code "124") (name "unconnected-(C-VL2{slash}RL2-Pad22)") (class "Default")
      (node (ref "C") (pin "22") (pinfunction "VL2/RL2_22") (pintype "passive"))
    )
    (net (code "125") (name "unconnected-(C-VL3{slash}RL3-Pad5)") (class "Default")
      (node (ref "C") (pin "5") (pinfunction "VL3/RL3_5") (pintype "passive"))
    )
    (net (code "126") (name "unconnected-(C-~{WP}-Pad12)") (class "Default")
      (node (ref "C") (pin "12") (pinfunction "~{WP}_12") (pintype "passive"))
    )
    (net (code "127") (name "unconnected-(D-NC-Pad1)") (class "Default")
      (node (ref "D") (pin "1") (pinfunction "NC_1") (pintype "no_connect"))
    )
    (net (code "128") (name "unconnected-(D-VL0{slash}RL0-Pad8)") (class "Default")
      (node (ref "D") (pin "8") (pinfunction "VL0/RL0_8") (pintype "passive"))
    )
    (net (code "129") (name "unconnected-(D-VL1{slash}RW1-Pad15)") (class "Default")
      (node (ref "D") (pin "15") (pinfunction "VL1/RW1_15") (pintype "passive"))
    )
    (net (code "130") (name "unconnected-(D-VL2{slash}RL2-Pad22)") (class "Default")
      (node (ref "D") (pin "22") (pinfunction "VL2/RL2_22") (pintype "passive"))
    )
    (net (code "131") (name "unconnected-(D-VW3{slash}RW3-Pad3)") (class "Default")
      (node (ref "D") (pin "3") (pinfunction "VW3/RW3_3") (pintype "passive"))
    )
    (net (code "132") (name "unconnected-(D-~{WP}-Pad12)") (class "Default")
      (node (ref "D") (pin "12") (pinfunction "~{WP}_12") (pintype "passive"))
    )
    (net (code "133") (name "unconnected-(POTA-NC-Pad1)") (class "Default")
      (node (ref "POTA") (pin "1") (pinfunction "NC_1") (pintype "no_connect"))
    )
    (net (code "134") (name "unconnected-(POTA-VL0{slash}RL0-Pad8)") (class "Default")
      (node (ref "POTA") (pin "8") (pinfunction "VL0/RL0_8") (pintype "passive"))
    )
    (net (code "135") (name "unconnected-(POTA-VL1{slash}RW1-Pad15)") (class "Default")
      (node (ref "POTA") (pin "15") (pinfunction "VL1/RW1_15") (pintype "passive"))
    )
    (net (code "136") (name "unconnected-(POTA-VL2{slash}RL2-Pad22)") (class "Default")
      (node (ref "POTA") (pin "22") (pinfunction "VL2/RL2_22") (pintype "passive"))
    )
    (net (code "137") (name "unconnected-(POTA-VL3{slash}RL3-Pad5)") (class "Default")
      (node (ref "POTA") (pin "5") (pinfunction "VL3/RL3_5") (pintype "passive"))
    )
    (net (code "138") (name "unconnected-(POTA-~{WP}-Pad12)") (class "Default")
      (node (ref "POTA") (pin "12") (pinfunction "~{WP}_12") (pintype "passive"))
    )
    (net (code "139") (name "unconnected-(POTB-NC-Pad1)") (class "Default")
      (node (ref "POTB") (pin "1") (pinfunction "NC_1") (pintype "no_connect"))
    )
    (net (code "140") (name "unconnected-(POTB-VL0{slash}RL0-Pad8)") (class "Default")
      (node (ref "POTB") (pin "8") (pinfunction "VL0/RL0_8") (pintype "passive"))
    )
    (net (code "141") (name "unconnected-(POTB-VL1{slash}RW1-Pad15)") (class "Default")
      (node (ref "POTB") (pin "15") (pinfunction "VL1/RW1_15") (pintype "passive"))
    )
    (net (code "142") (name "unconnected-(POTB-VL2{slash}RL2-Pad22)") (class "Default")
      (node (ref "POTB") (pin "22") (pinfunction "VL2/RL2_22") (pintype "passive"))
    )
    (net (code "143") (name "unconnected-(POTB-VL3{slash}RL3-Pad5)") (class "Default")
      (node (ref "POTB") (pin "5") (pinfunction "VL3/RL3_5") (pintype "passive"))
    )
    (net (code "144") (name "unconnected-(POTB-VW1{slash}RW1-Pad17)") (class "Default")
      (node (ref "POTB") (pin "17") (pinfunction "VW1/RW1_17") (pintype "passive"))
    )
    (net (code "145") (name "unconnected-(POTB-~{WP}-Pad12)") (class "Default")
      (node (ref "POTB") (pin "12") (pinfunction "~{WP}_12") (pintype "passive"))
    )
    (net (code "146") (name "unconnected-(SYS_IN-A7-Pad4)") (class "Default")
      (node (ref "SYS_IN") (pin "4") (pinfunction "A7_4") (pintype "bidirectional"))
    )
    (net (code "147") (name "unconnected-(SYS_OUT-A7-Pad4)") (class "Default")
      (node (ref "SYS_OUT") (pin "4") (pinfunction "A7_4") (pintype "bidirectional"))
    )
  )
)
